# SM3320-BATT-EV.net
KiCad netlist of a schematic drawn in Altium Designer
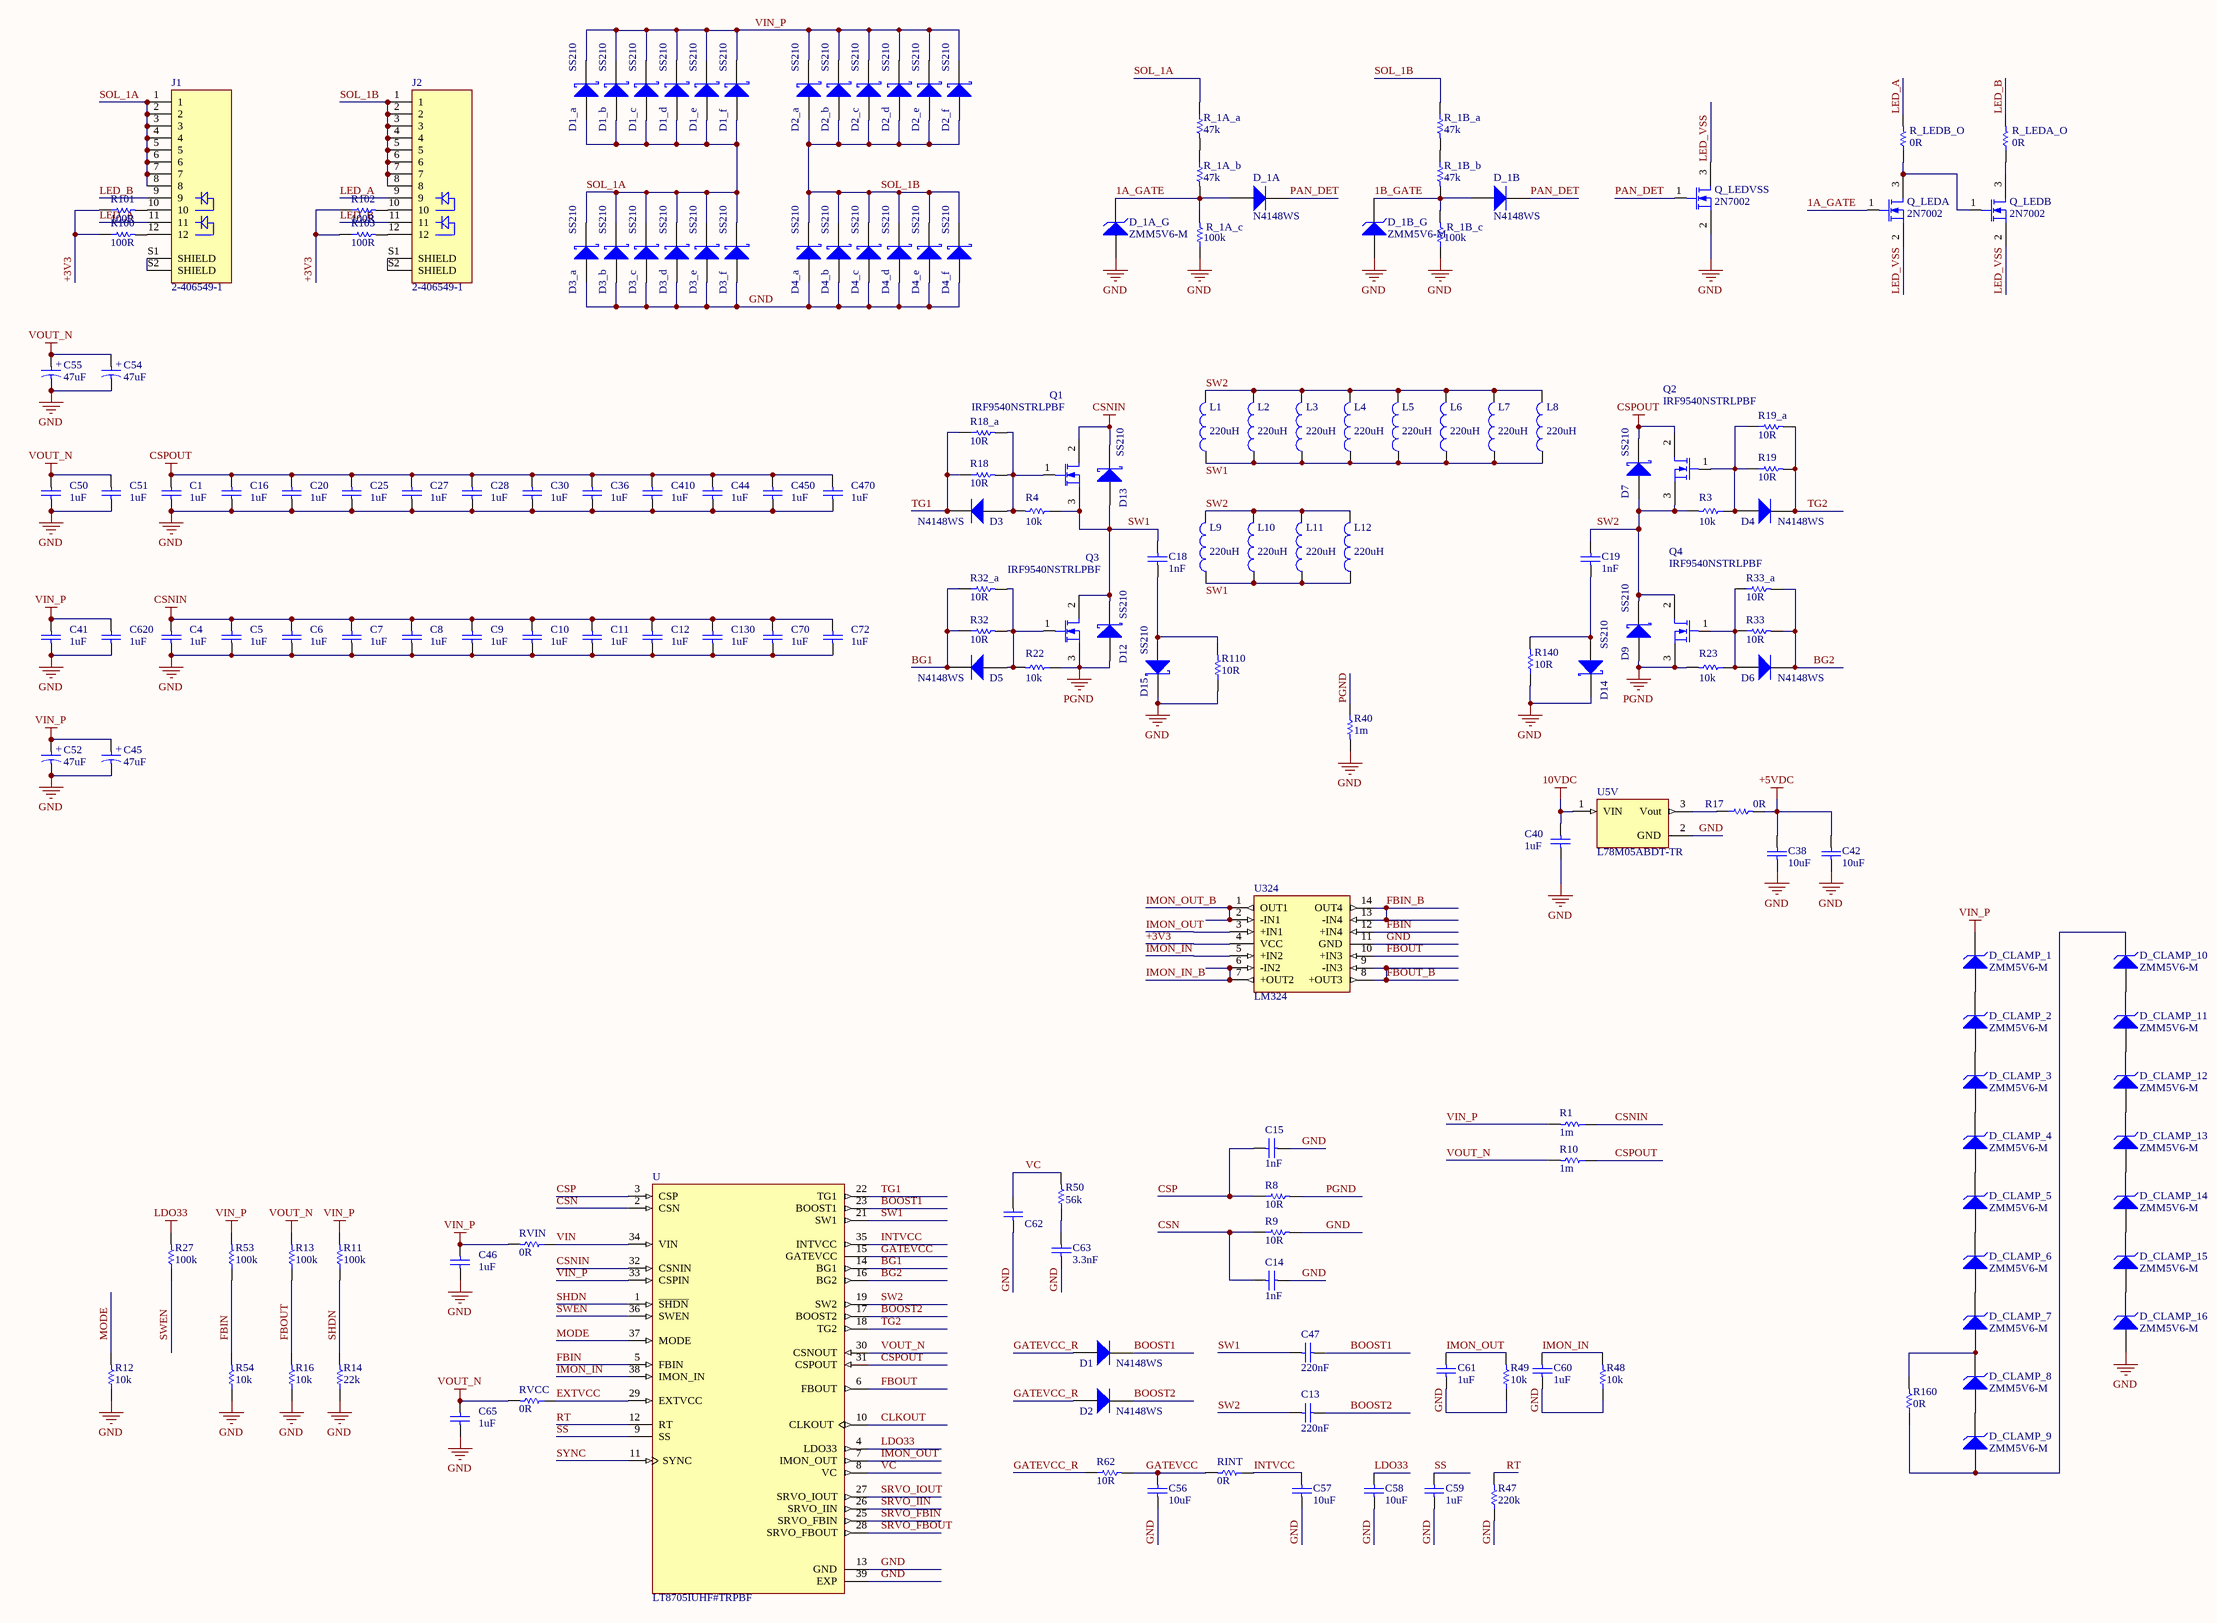
[diagram p0: SM3320-BATT-EV.SchDoc]

(export (version "E")
  (design (tool "Eeschema 10.0.6"))
  (components
    (comp (ref "C1")
      (value "1uF")
      (footprint "C_1206")
      (description "C - CAPACITOR - MLCC - 1uF - 100V - 1206 - X7R")
      (fields (field (name "LCSC PART #") "C91151") (field (name "Comment") "1206B105K101NT"))
      (libsource (lib "JLC_PCB") (part "1206B105K101NT"))
    )
    (comp (ref "C4")
      (value "1uF")
      (footprint "C_1206")
      (description "C - CAPACITOR - MLCC - 1uF - 100V - 1206 - X7R")
      (fields (field (name "LCSC PART #") "C91151") (field (name "Comment") "1206B105K101NT"))
      (libsource (lib "JLC_PCB") (part "1206B105K101NT"))
    )
    (comp (ref "C5")
      (value "1uF")
      (footprint "C_1206")
      (description "C - CAPACITOR - MLCC - 1uF - 100V - 1206 - X7R")
      (fields (field (name "LCSC PART #") "C91151") (field (name "Comment") "1206B105K101NT"))
      (libsource (lib "JLC_PCB") (part "1206B105K101NT"))
    )
    (comp (ref "C6")
      (value "1uF")
      (footprint "C_1206")
      (description "C - CAPACITOR - MLCC - 1uF - 100V - 1206 - X7R")
      (fields (field (name "LCSC PART #") "C91151") (field (name "Comment") "1206B105K101NT"))
      (libsource (lib "JLC_PCB") (part "1206B105K101NT"))
    )
    (comp (ref "C7")
      (value "1uF")
      (footprint "C_1206")
      (description "C - CAPACITOR - MLCC - 1uF - 100V - 1206 - X7R")
      (fields (field (name "LCSC PART #") "C91151") (field (name "Comment") "1206B105K101NT"))
      (libsource (lib "JLC_PCB") (part "1206B105K101NT"))
    )
    (comp (ref "C8")
      (value "1uF")
      (footprint "C_1206")
      (description "C - CAPACITOR - MLCC - 1uF - 100V - 1206 - X7R")
      (fields (field (name "LCSC PART #") "C91151") (field (name "Comment") "1206B105K101NT"))
      (libsource (lib "JLC_PCB") (part "1206B105K101NT"))
    )
    (comp (ref "C9")
      (value "1uF")
      (footprint "C_1206")
      (description "C - CAPACITOR - MLCC - 1uF - 100V - 1206 - X7R")
      (fields (field (name "LCSC PART #") "C91151") (field (name "Comment") "1206B105K101NT"))
      (libsource (lib "JLC_PCB") (part "1206B105K101NT"))
    )
    (comp (ref "C10")
      (value "1uF")
      (footprint "C_1206")
      (description "C - CAPACITOR - MLCC - 1uF - 100V - 1206 - X7R")
      (fields (field (name "LCSC PART #") "C91151") (field (name "Comment") "1206B105K101NT"))
      (libsource (lib "JLC_PCB") (part "1206B105K101NT"))
    )
    (comp (ref "C11")
      (value "1uF")
      (footprint "C_1206")
      (description "C - CAPACITOR - MLCC - 1uF - 100V - 1206 - X7R")
      (fields (field (name "LCSC PART #") "C91151") (field (name "Comment") "1206B105K101NT"))
      (libsource (lib "JLC_PCB") (part "1206B105K101NT"))
    )
    (comp (ref "C12")
      (value "1uF")
      (footprint "C_1206")
      (description "C - CAPACITOR - MLCC - 1uF - 100V - 1206 - X7R")
      (fields (field (name "LCSC PART #") "C91151") (field (name "Comment") "1206B105K101NT"))
      (libsource (lib "JLC_PCB") (part "1206B105K101NT"))
    )
    (comp (ref "C13")
      (value "220nF")
      (footprint "C_0402")
      (description "C - CAPACITOR - MLCC - 220nF - 16V - 0402")
      (fields (field (name "LCSC PART #") "C16772") (field (name "Comment") "CL05B224KO5NNNC"))
      (libsource (lib "JLC_PCB") (part "CL05B224KO5NNNC"))
    )
    (comp (ref "C14")
      (value "1nF")
      (footprint "C_0402")
      (description "C - CAPACITOR - MLCC - 1nF - 50V - 0402")
      (fields (field (name "LCSC PART #") "C1523") (field (name "Comment") "0402B102K500NT"))
      (libsource (lib "JLC_PCB") (part "0402B102K500NT"))
    )
    (comp (ref "C15")
      (value "1nF")
      (footprint "C_0402")
      (description "C - CAPACITOR - MLCC - 1nF - 50V - 0402")
      (fields (field (name "LCSC PART #") "C1523") (field (name "Comment") "0402B102K500NT"))
      (libsource (lib "JLC_PCB") (part "0402B102K500NT"))
    )
    (comp (ref "C16")
      (value "1uF")
      (footprint "C_1206")
      (description "C - CAPACITOR - MLCC - 1uF - 100V - 1206 - X7R")
      (fields (field (name "LCSC PART #") "C91151") (field (name "Comment") "1206B105K101NT"))
      (libsource (lib "JLC_PCB") (part "1206B105K101NT"))
    )
    (comp (ref "C18")
      (value "1nF")
      (footprint "C_1206")
      (description "C - CAPACITOR - MLCC - 1nF - 2000V - 1206 - X7R")
      (fields (field (name "LCSC PART #") "C9196") (field (name "Comment") "1206B102K202NT"))
      (libsource (lib "JLC_PCB") (part "1206B102K202NT"))
    )
    (comp (ref "C19")
      (value "1nF")
      (footprint "C_1206")
      (description "C - CAPACITOR - MLCC - 1nF - 2000V - 1206 - X7R")
      (fields (field (name "LCSC PART #") "C9196") (field (name "Comment") "1206B102K202NT"))
      (libsource (lib "JLC_PCB") (part "1206B102K202NT"))
    )
    (comp (ref "C20")
      (value "1uF")
      (footprint "C_1206")
      (description "C - CAPACITOR - MLCC - 1uF - 100V - 1206 - X7R")
      (fields (field (name "LCSC PART #") "C91151") (field (name "Comment") "1206B105K101NT"))
      (libsource (lib "JLC_PCB") (part "1206B105K101NT"))
    )
    (comp (ref "C25")
      (value "1uF")
      (footprint "C_1206")
      (description "C - CAPACITOR - MLCC - 1uF - 100V - 1206 - X7R")
      (fields (field (name "LCSC PART #") "C91151") (field (name "Comment") "1206B105K101NT"))
      (libsource (lib "JLC_PCB") (part "1206B105K101NT"))
    )
    (comp (ref "C27")
      (value "1uF")
      (footprint "C_1206")
      (description "C - CAPACITOR - MLCC - 1uF - 100V - 1206 - X7R")
      (fields (field (name "LCSC PART #") "C91151") (field (name "Comment") "1206B105K101NT"))
      (libsource (lib "JLC_PCB") (part "1206B105K101NT"))
    )
    (comp (ref "C28")
      (value "1uF")
      (footprint "C_1206")
      (description "C - CAPACITOR - MLCC - 1uF - 100V - 1206 - X7R")
      (fields (field (name "LCSC PART #") "C91151") (field (name "Comment") "1206B105K101NT"))
      (libsource (lib "JLC_PCB") (part "1206B105K101NT"))
    )
    (comp (ref "C30")
      (value "1uF")
      (footprint "C_1206")
      (description "C - CAPACITOR - MLCC - 1uF - 100V - 1206 - X7R")
      (fields (field (name "LCSC PART #") "C91151") (field (name "Comment") "1206B105K101NT"))
      (libsource (lib "JLC_PCB") (part "1206B105K101NT"))
    )
    (comp (ref "C36")
      (value "1uF")
      (footprint "C_1206")
      (description "C - CAPACITOR - MLCC - 1uF - 100V - 1206 - X7R")
      (fields (field (name "LCSC PART #") "C91151") (field (name "Comment") "1206B105K101NT"))
      (libsource (lib "JLC_PCB") (part "1206B105K101NT"))
    )
    (comp (ref "C38")
      (value "10uF")
      (footprint "C_0402")
      (description "C - CAPACITOR - MLCC - 10uF - 6.3V - 0402")
      (fields (field (name "LCSC PART #") "C15525") (field (name "Comment") "CL05A106MQ5NUNC"))
      (libsource (lib "JLC_PCB") (part "CL05A106MQ5NUNC"))
    )
    (comp (ref "C40")
      (value "1uF")
      (footprint "C_0402")
      (description "C - CAPACITOR - MLCC - 1uF - 25V - 0402")
      (fields (field (name "LCSC PART #") "C52923") (field (name "Comment") "CL05A105KA5NQNC"))
      (libsource (lib "JLC_PCB") (part "CL05A105KA5NQNC"))
    )
    (comp (ref "C41")
      (value "1uF")
      (footprint "C_1206")
      (description "C - CAPACITOR - MLCC - 1uF - 100V - 1206 - X7R")
      (fields (field (name "LCSC PART #") "C91151") (field (name "Comment") "1206B105K101NT"))
      (libsource (lib "JLC_PCB") (part "1206B105K101NT"))
    )
    (comp (ref "C42")
      (value "10uF")
      (footprint "C_0402")
      (description "C - CAPACITOR - MLCC - 10uF - 6.3V - 0402")
      (fields (field (name "LCSC PART #") "C15525") (field (name "Comment") "CL05A106MQ5NUNC"))
      (libsource (lib "JLC_PCB") (part "CL05A106MQ5NUNC"))
    )
    (comp (ref "C44")
      (value "1uF")
      (footprint "C_1206")
      (description "C - CAPACITOR - MLCC - 1uF - 100V - 1206 - X7R")
      (fields (field (name "LCSC PART #") "C91151") (field (name "Comment") "1206B105K101NT"))
      (libsource (lib "JLC_PCB") (part "1206B105K101NT"))
    )
    (comp (ref "C45")
      (value "47uF")
      (footprint "C_CAN_1010")
      (description "C - CAPACITOR - ELECTROLYTIC - 47uF - 100V")
      (fields (field (name "LCSC PART #") "C164068") (field (name "Comment") "VZH470M2ATR-1010"))
      (libsource (lib "JLC_PCB") (part "VZH470M2ATR-1010"))
    )
    (comp (ref "C46")
      (value "1uF")
      (footprint "C_1206")
      (description "C - CAPACITOR - MLCC - 1uF - 100V - 1206 - X7R")
      (fields (field (name "LCSC PART #") "C91151") (field (name "Comment") "1206B105K101NT"))
      (libsource (lib "JLC_PCB") (part "1206B105K101NT"))
    )
    (comp (ref "C47")
      (value "220nF")
      (footprint "C_0402")
      (description "C - CAPACITOR - MLCC - 220nF - 16V - 0402")
      (fields (field (name "LCSC PART #") "C16772") (field (name "Comment") "CL05B224KO5NNNC"))
      (libsource (lib "JLC_PCB") (part "CL05B224KO5NNNC"))
    )
    (comp (ref "C50")
      (value "1uF")
      (footprint "C_1206")
      (description "C - CAPACITOR - MLCC - 1uF - 100V - 1206 - X7R")
      (fields (field (name "LCSC PART #") "C91151") (field (name "Comment") "1206B105K101NT"))
      (libsource (lib "JLC_PCB") (part "1206B105K101NT"))
    )
    (comp (ref "C51")
      (value "1uF")
      (footprint "C_1206")
      (description "C - CAPACITOR - MLCC - 1uF - 100V - 1206 - X7R")
      (fields (field (name "LCSC PART #") "C91151") (field (name "Comment") "1206B105K101NT"))
      (libsource (lib "JLC_PCB") (part "1206B105K101NT"))
    )
    (comp (ref "C52")
      (value "47uF")
      (footprint "C_CAN_1010")
      (description "C - CAPACITOR - ELECTROLYTIC - 47uF - 100V")
      (fields (field (name "LCSC PART #") "C164068") (field (name "Comment") "VZH470M2ATR-1010"))
      (libsource (lib "JLC_PCB") (part "VZH470M2ATR-1010"))
    )
    (comp (ref "C54")
      (value "47uF")
      (footprint "C_CAN_1010")
      (description "C - CAPACITOR - ELECTROLYTIC - 47uF - 100V")
      (fields (field (name "LCSC PART #") "C164068") (field (name "Comment") "VZH470M2ATR-1010"))
      (libsource (lib "JLC_PCB") (part "VZH470M2ATR-1010"))
    )
    (comp (ref "C55")
      (value "47uF")
      (footprint "C_CAN_1010")
      (description "C - CAPACITOR - ELECTROLYTIC - 47uF - 100V")
      (fields (field (name "LCSC PART #") "C164068") (field (name "Comment") "VZH470M2ATR-1010"))
      (libsource (lib "JLC_PCB") (part "VZH470M2ATR-1010"))
    )
    (comp (ref "C56")
      (value "10uF")
      (footprint "C_0402")
      (description "C - CAPACITOR - MLCC - 10uF - 6.3V - 0402")
      (fields (field (name "LCSC PART #") "C15525") (field (name "Comment") "CL05A106MQ5NUNC"))
      (libsource (lib "JLC_PCB") (part "CL05A106MQ5NUNC"))
    )
    (comp (ref "C57")
      (value "10uF")
      (footprint "C_0402")
      (description "C - CAPACITOR - MLCC - 10uF - 6.3V - 0402")
      (fields (field (name "LCSC PART #") "C15525") (field (name "Comment") "CL05A106MQ5NUNC"))
      (libsource (lib "JLC_PCB") (part "CL05A106MQ5NUNC"))
    )
    (comp (ref "C58")
      (value "10uF")
      (footprint "C_0402")
      (description "C - CAPACITOR - MLCC - 10uF - 6.3V - 0402")
      (fields (field (name "LCSC PART #") "C15525") (field (name "Comment") "CL05A106MQ5NUNC"))
      (libsource (lib "JLC_PCB") (part "CL05A106MQ5NUNC"))
    )
    (comp (ref "C59")
      (value "1uF")
      (footprint "C_0402")
      (description "C - CAPACITOR - MLCC - 1uF - 25V - 0402")
      (fields (field (name "LCSC PART #") "C52923") (field (name "Comment") "CL05A105KA5NQNC"))
      (libsource (lib "JLC_PCB") (part "CL05A105KA5NQNC"))
    )
    (comp (ref "C60")
      (value "1uF")
      (footprint "C_0402")
      (description "C - CAPACITOR - MLCC - 1uF - 25V - 0402")
      (fields (field (name "LCSC PART #") "C52923") (field (name "Comment") "CL05A105KA5NQNC"))
      (libsource (lib "JLC_PCB") (part "CL05A105KA5NQNC"))
    )
    (comp (ref "C61")
      (value "1uF")
      (footprint "C_0402")
      (description "C - CAPACITOR - MLCC - 1uF - 25V - 0402")
      (fields (field (name "LCSC PART #") "C52923") (field (name "Comment") "CL05A105KA5NQNC"))
      (libsource (lib "JLC_PCB") (part "CL05A105KA5NQNC"))
    )
    (comp (ref "C62")
      (value "0402CG101J500NT")
      (footprint "C_0402")
      (description "C - CAPACITOR - MLCC - 100pF - 50V - 0402")
      (fields (field (name "LCSC PART #") "C1546"))
      (libsource (lib "JLC_PCB") (part "0402CG101J500NT"))
    )
    (comp (ref "C63")
      (value "3.3nF")
      (footprint "C_0402")
      (description "C - CAPACITOR - MLCC - 3.3nF - 50V - 0402")
      (fields (field (name "LCSC PART #") "C26404") (field (name "Comment") "CL05B332KB5NNNC"))
      (libsource (lib "JLC_PCB") (part "CL05B332KB5NNNC"))
    )
    (comp (ref "C65")
      (value "1uF")
      (footprint "C_1206")
      (description "C - CAPACITOR - MLCC - 1uF - 100V - 1206 - X7R")
      (fields (field (name "LCSC PART #") "C91151") (field (name "Comment") "1206B105K101NT"))
      (libsource (lib "JLC_PCB") (part "1206B105K101NT"))
    )
    (comp (ref "C70")
      (value "1uF")
      (footprint "C_1206")
      (description "C - CAPACITOR - MLCC - 1uF - 100V - 1206 - X7R")
      (fields (field (name "LCSC PART #") "C91151") (field (name "Comment") "1206B105K101NT"))
      (libsource (lib "JLC_PCB") (part "1206B105K101NT"))
    )
    (comp (ref "C72")
      (value "1uF")
      (footprint "C_1206")
      (description "C - CAPACITOR - MLCC - 1uF - 100V - 1206 - X7R")
      (fields (field (name "LCSC PART #") "C91151") (field (name "Comment") "1206B105K101NT"))
      (libsource (lib "JLC_PCB") (part "1206B105K101NT"))
    )
    (comp (ref "C130")
      (value "1uF")
      (footprint "C_1206")
      (description "C - CAPACITOR - MLCC - 1uF - 100V - 1206 - X7R")
      (fields (field (name "LCSC PART #") "C91151") (field (name "Comment") "1206B105K101NT"))
      (libsource (lib "JLC_PCB") (part "1206B105K101NT"))
    )
    (comp (ref "C410")
      (value "1uF")
      (footprint "C_1206")
      (description "C - CAPACITOR - MLCC - 1uF - 100V - 1206 - X7R")
      (fields (field (name "LCSC PART #") "C91151") (field (name "Comment") "1206B105K101NT"))
      (libsource (lib "JLC_PCB") (part "1206B105K101NT"))
    )
    (comp (ref "C450")
      (value "1uF")
      (footprint "C_1206")
      (description "C - CAPACITOR - MLCC - 1uF - 100V - 1206 - X7R")
      (fields (field (name "LCSC PART #") "C91151") (field (name "Comment") "1206B105K101NT"))
      (libsource (lib "JLC_PCB") (part "1206B105K101NT"))
    )
    (comp (ref "C470")
      (value "1uF")
      (footprint "C_1206")
      (description "C - CAPACITOR - MLCC - 1uF - 100V - 1206 - X7R")
      (fields (field (name "LCSC PART #") "C91151") (field (name "Comment") "1206B105K101NT"))
      (libsource (lib "JLC_PCB") (part "1206B105K101NT"))
    )
    (comp (ref "C620")
      (value "1uF")
      (footprint "C_1206")
      (description "C - CAPACITOR - MLCC - 1uF - 100V - 1206 - X7R")
      (fields (field (name "LCSC PART #") "C91151") (field (name "Comment") "1206B105K101NT"))
      (libsource (lib "JLC_PCB") (part "1206B105K101NT"))
    )
    (comp (ref "D1")
      (value "N4148WS")
      (footprint "SOD-323")
      (description "D - DIODE - FAST TRR - 100V - 150mA - 4ns")
      (fields (field (name "LCSC PART #") "C2128"))
      (libsource (lib "JLC_PCB") (part "N4148WS"))
    )
    (comp (ref "D1_a")
      (value "SS210")
      (footprint "DO-214AC")
      (description "D - DIODE - SCHOTTKY - 100V - 2A")
      (fields (field (name "LCSC PART #") "C14996"))
      (libsource (lib "JLC_PCB") (part "SS210"))
    )
    (comp (ref "D1_b")
      (value "SS210")
      (footprint "DO-214AC")
      (description "D - DIODE - SCHOTTKY - 100V - 2A")
      (fields (field (name "LCSC PART #") "C14996"))
      (libsource (lib "JLC_PCB") (part "SS210"))
    )
    (comp (ref "D1_c")
      (value "SS210")
      (footprint "DO-214AC")
      (description "D - DIODE - SCHOTTKY - 100V - 2A")
      (fields (field (name "LCSC PART #") "C14996"))
      (libsource (lib "JLC_PCB") (part "SS210"))
    )
    (comp (ref "D1_d")
      (value "SS210")
      (footprint "DO-214AC")
      (description "D - DIODE - SCHOTTKY - 100V - 2A")
      (fields (field (name "LCSC PART #") "C14996"))
      (libsource (lib "JLC_PCB") (part "SS210"))
    )
    (comp (ref "D1_e")
      (value "SS210")
      (footprint "DO-214AC")
      (description "D - DIODE - SCHOTTKY - 100V - 2A")
      (fields (field (name "LCSC PART #") "C14996"))
      (libsource (lib "JLC_PCB") (part "SS210"))
    )
    (comp (ref "D1_f")
      (value "SS210")
      (footprint "DO-214AC")
      (description "D - DIODE - SCHOTTKY - 100V - 2A")
      (fields (field (name "LCSC PART #") "C14996"))
      (libsource (lib "JLC_PCB") (part "SS210"))
    )
    (comp (ref "D2")
      (value "N4148WS")
      (footprint "SOD-323")
      (description "D - DIODE - FAST TRR - 100V - 150mA - 4ns")
      (fields (field (name "LCSC PART #") "C2128"))
      (libsource (lib "JLC_PCB") (part "N4148WS"))
    )
    (comp (ref "D2_a")
      (value "SS210")
      (footprint "DO-214AC")
      (description "D - DIODE - SCHOTTKY - 100V - 2A")
      (fields (field (name "LCSC PART #") "C14996"))
      (libsource (lib "JLC_PCB") (part "SS210"))
    )
    (comp (ref "D2_b")
      (value "SS210")
      (footprint "DO-214AC")
      (description "D - DIODE - SCHOTTKY - 100V - 2A")
      (fields (field (name "LCSC PART #") "C14996"))
      (libsource (lib "JLC_PCB") (part "SS210"))
    )
    (comp (ref "D2_c")
      (value "SS210")
      (footprint "DO-214AC")
      (description "D - DIODE - SCHOTTKY - 100V - 2A")
      (fields (field (name "LCSC PART #") "C14996"))
      (libsource (lib "JLC_PCB") (part "SS210"))
    )
    (comp (ref "D2_d")
      (value "SS210")
      (footprint "DO-214AC")
      (description "D - DIODE - SCHOTTKY - 100V - 2A")
      (fields (field (name "LCSC PART #") "C14996"))
      (libsource (lib "JLC_PCB") (part "SS210"))
    )
    (comp (ref "D2_e")
      (value "SS210")
      (footprint "DO-214AC")
      (description "D - DIODE - SCHOTTKY - 100V - 2A")
      (fields (field (name "LCSC PART #") "C14996"))
      (libsource (lib "JLC_PCB") (part "SS210"))
    )
    (comp (ref "D2_f")
      (value "SS210")
      (footprint "DO-214AC")
      (description "D - DIODE - SCHOTTKY - 100V - 2A")
      (fields (field (name "LCSC PART #") "C14996"))
      (libsource (lib "JLC_PCB") (part "SS210"))
    )
    (comp (ref "D3")
      (value "N4148WS")
      (footprint "SOD-323")
      (description "D - DIODE - FAST TRR - 100V - 150mA - 4ns")
      (fields (field (name "LCSC PART #") "C2128"))
      (libsource (lib "JLC_PCB") (part "N4148WS"))
    )
    (comp (ref "D3_a")
      (value "SS210")
      (footprint "DO-214AC")
      (description "D - DIODE - SCHOTTKY - 100V - 2A")
      (fields (field (name "LCSC PART #") "C14996"))
      (libsource (lib "JLC_PCB") (part "SS210"))
    )
    (comp (ref "D3_b")
      (value "SS210")
      (footprint "DO-214AC")
      (description "D - DIODE - SCHOTTKY - 100V - 2A")
      (fields (field (name "LCSC PART #") "C14996"))
      (libsource (lib "JLC_PCB") (part "SS210"))
    )
    (comp (ref "D3_c")
      (value "SS210")
      (footprint "DO-214AC")
      (description "D - DIODE - SCHOTTKY - 100V - 2A")
      (fields (field (name "LCSC PART #") "C14996"))
      (libsource (lib "JLC_PCB") (part "SS210"))
    )
    (comp (ref "D3_d")
      (value "SS210")
      (footprint "DO-214AC")
      (description "D - DIODE - SCHOTTKY - 100V - 2A")
      (fields (field (name "LCSC PART #") "C14996"))
      (libsource (lib "JLC_PCB") (part "SS210"))
    )
    (comp (ref "D3_e")
      (value "SS210")
      (footprint "DO-214AC")
      (description "D - DIODE - SCHOTTKY - 100V - 2A")
      (fields (field (name "LCSC PART #") "C14996"))
      (libsource (lib "JLC_PCB") (part "SS210"))
    )
    (comp (ref "D3_f")
      (value "SS210")
      (footprint "DO-214AC")
      (description "D - DIODE - SCHOTTKY - 100V - 2A")
      (fields (field (name "LCSC PART #") "C14996"))
      (libsource (lib "JLC_PCB") (part "SS210"))
    )
    (comp (ref "D4")
      (value "N4148WS")
      (footprint "SOD-323")
      (description "D - DIODE - FAST TRR - 100V - 150mA - 4ns")
      (fields (field (name "LCSC PART #") "C2128"))
      (libsource (lib "JLC_PCB") (part "N4148WS"))
    )
    (comp (ref "D4_a")
      (value "SS210")
      (footprint "DO-214AC")
      (description "D - DIODE - SCHOTTKY - 100V - 2A")
      (fields (field (name "LCSC PART #") "C14996"))
      (libsource (lib "JLC_PCB") (part "SS210"))
    )
    (comp (ref "D4_b")
      (value "SS210")
      (footprint "DO-214AC")
      (description "D - DIODE - SCHOTTKY - 100V - 2A")
      (fields (field (name "LCSC PART #") "C14996"))
      (libsource (lib "JLC_PCB") (part "SS210"))
    )
    (comp (ref "D4_c")
      (value "SS210")
      (footprint "DO-214AC")
      (description "D - DIODE - SCHOTTKY - 100V - 2A")
      (fields (field (name "LCSC PART #") "C14996"))
      (libsource (lib "JLC_PCB") (part "SS210"))
    )
    (comp (ref "D4_d")
      (value "SS210")
      (footprint "DO-214AC")
      (description "D - DIODE - SCHOTTKY - 100V - 2A")
      (fields (field (name "LCSC PART #") "C14996"))
      (libsource (lib "JLC_PCB") (part "SS210"))
    )
    (comp (ref "D4_e")
      (value "SS210")
      (footprint "DO-214AC")
      (description "D - DIODE - SCHOTTKY - 100V - 2A")
      (fields (field (name "LCSC PART #") "C14996"))
      (libsource (lib "JLC_PCB") (part "SS210"))
    )
    (comp (ref "D4_f")
      (value "SS210")
      (footprint "DO-214AC")
      (description "D - DIODE - SCHOTTKY - 100V - 2A")
      (fields (field (name "LCSC PART #") "C14996"))
      (libsource (lib "JLC_PCB") (part "SS210"))
    )
    (comp (ref "D5")
      (value "N4148WS")
      (footprint "SOD-323")
      (description "D - DIODE - FAST TRR - 100V - 150mA - 4ns")
      (fields (field (name "LCSC PART #") "C2128"))
      (libsource (lib "JLC_PCB") (part "N4148WS"))
    )
    (comp (ref "D6")
      (value "N4148WS")
      (footprint "SOD-323")
      (description "D - DIODE - FAST TRR - 100V - 150mA - 4ns")
      (fields (field (name "LCSC PART #") "C2128"))
      (libsource (lib "JLC_PCB") (part "N4148WS"))
    )
    (comp (ref "D7")
      (value "SS210")
      (footprint "DO-214AC")
      (description "D - DIODE - SCHOTTKY - 100V - 2A")
      (fields (field (name "LCSC PART #") "C14996"))
      (libsource (lib "JLC_PCB") (part "SS210"))
    )
    (comp (ref "D9")
      (value "SS210")
      (footprint "DO-214AC")
      (description "D - DIODE - SCHOTTKY - 100V - 2A")
      (fields (field (name "LCSC PART #") "C14996"))
      (libsource (lib "JLC_PCB") (part "SS210"))
    )
    (comp (ref "D12")
      (value "SS210")
      (footprint "DO-214AC")
      (description "D - DIODE - SCHOTTKY - 100V - 2A")
      (fields (field (name "LCSC PART #") "C14996"))
      (libsource (lib "JLC_PCB") (part "SS210"))
    )
    (comp (ref "D13")
      (value "SS210")
      (footprint "DO-214AC")
      (description "D - DIODE - SCHOTTKY - 100V - 2A")
      (fields (field (name "LCSC PART #") "C14996"))
      (libsource (lib "JLC_PCB") (part "SS210"))
    )
    (comp (ref "D14")
      (value "SS210")
      (footprint "DO-214AC")
      (description "D - DIODE - SCHOTTKY - 100V - 2A")
      (fields (field (name "LCSC PART #") "C14996"))
      (libsource (lib "JLC_PCB") (part "SS210"))
    )
    (comp (ref "D15")
      (value "SS210")
      (footprint "DO-214AC")
      (description "D - DIODE - SCHOTTKY - 100V - 2A")
      (fields (field (name "LCSC PART #") "C14996"))
      (libsource (lib "JLC_PCB") (part "SS210"))
    )
    (comp (ref "D_1A")
      (value "N4148WS")
      (footprint "SOD-323")
      (description "D - DIODE - FAST TRR - 100V - 150mA - 4ns")
      (fields (field (name "LCSC PART #") "C2128"))
      (libsource (lib "JLC_PCB") (part "N4148WS"))
    )
    (comp (ref "D_1A_G")
      (value "ZMM5V6-M")
      (footprint "DO-213AA")
      (description "D - DIODE - ZENER - 5.6V - 500mW")
      (fields (field (name "LCSC PART #") "C8062"))
      (libsource (lib "JLC_PCB") (part "ZMM5V6-M"))
    )
    (comp (ref "D_1B")
      (value "N4148WS")
      (footprint "SOD-323")
      (description "D - DIODE - FAST TRR - 100V - 150mA - 4ns")
      (fields (field (name "LCSC PART #") "C2128"))
      (libsource (lib "JLC_PCB") (part "N4148WS"))
    )
    (comp (ref "D_1B_G")
      (value "ZMM5V6-M")
      (footprint "DO-213AA")
      (description "D - DIODE - ZENER - 5.6V - 500mW")
      (fields (field (name "LCSC PART #") "C8062"))
      (libsource (lib "JLC_PCB") (part "ZMM5V6-M"))
    )
    (comp (ref "D_CLAMP_1")
      (value "ZMM5V6-M")
      (footprint "DO-213AA")
      (description "D - DIODE - ZENER - 5.6V - 500mW")
      (fields (field (name "LCSC PART #") "C8062"))
      (libsource (lib "JLC_PCB") (part "ZMM5V6-M"))
    )
    (comp (ref "D_CLAMP_2")
      (value "ZMM5V6-M")
      (footprint "DO-213AA")
      (description "D - DIODE - ZENER - 5.6V - 500mW")
      (fields (field (name "LCSC PART #") "C8062"))
      (libsource (lib "JLC_PCB") (part "ZMM5V6-M"))
    )
    (comp (ref "D_CLAMP_3")
      (value "ZMM5V6-M")
      (footprint "DO-213AA")
      (description "D - DIODE - ZENER - 5.6V - 500mW")
      (fields (field (name "LCSC PART #") "C8062"))
      (libsource (lib "JLC_PCB") (part "ZMM5V6-M"))
    )
    (comp (ref "D_CLAMP_4")
      (value "ZMM5V6-M")
      (footprint "DO-213AA")
      (description "D - DIODE - ZENER - 5.6V - 500mW")
      (fields (field (name "LCSC PART #") "C8062"))
      (libsource (lib "JLC_PCB") (part "ZMM5V6-M"))
    )
    (comp (ref "D_CLAMP_5")
      (value "ZMM5V6-M")
      (footprint "DO-213AA")
      (description "D - DIODE - ZENER - 5.6V - 500mW")
      (fields (field (name "LCSC PART #") "C8062"))
      (libsource (lib "JLC_PCB") (part "ZMM5V6-M"))
    )
    (comp (ref "D_CLAMP_6")
      (value "ZMM5V6-M")
      (footprint "DO-213AA")
      (description "D - DIODE - ZENER - 5.6V - 500mW")
      (fields (field (name "LCSC PART #") "C8062"))
      (libsource (lib "JLC_PCB") (part "ZMM5V6-M"))
    )
    (comp (ref "D_CLAMP_7")
      (value "ZMM5V6-M")
      (footprint "DO-213AA")
      (description "D - DIODE - ZENER - 5.6V - 500mW")
      (fields (field (name "LCSC PART #") "C8062"))
      (libsource (lib "JLC_PCB") (part "ZMM5V6-M"))
    )
    (comp (ref "D_CLAMP_8")
      (value "ZMM5V6-M")
      (footprint "DO-213AA")
      (description "D - DIODE - ZENER - 5.6V - 500mW")
      (fields (field (name "LCSC PART #") "C8062"))
      (libsource (lib "JLC_PCB") (part "ZMM5V6-M"))
    )
    (comp (ref "D_CLAMP_9")
      (value "ZMM5V6-M")
      (footprint "DO-213AA")
      (description "D - DIODE - ZENER - 5.6V - 500mW")
      (fields (field (name "LCSC PART #") "C8062"))
      (libsource (lib "JLC_PCB") (part "ZMM5V6-M"))
    )
    (comp (ref "D_CLAMP_10")
      (value "ZMM5V6-M")
      (footprint "DO-213AA")
      (description "D - DIODE - ZENER - 5.6V - 500mW")
      (fields (field (name "LCSC PART #") "C8062"))
      (libsource (lib "JLC_PCB") (part "ZMM5V6-M"))
    )
    (comp (ref "D_CLAMP_11")
      (value "ZMM5V6-M")
      (footprint "DO-213AA")
      (description "D - DIODE - ZENER - 5.6V - 500mW")
      (fields (field (name "LCSC PART #") "C8062"))
      (libsource (lib "JLC_PCB") (part "ZMM5V6-M"))
    )
    (comp (ref "D_CLAMP_12")
      (value "ZMM5V6-M")
      (footprint "DO-213AA")
      (description "D - DIODE - ZENER - 5.6V - 500mW")
      (fields (field (name "LCSC PART #") "C8062"))
      (libsource (lib "JLC_PCB") (part "ZMM5V6-M"))
    )
    (comp (ref "D_CLAMP_13")
      (value "ZMM5V6-M")
      (footprint "DO-213AA")
      (description "D - DIODE - ZENER - 5.6V - 500mW")
      (fields (field (name "LCSC PART #") "C8062"))
      (libsource (lib "JLC_PCB") (part "ZMM5V6-M"))
    )
    (comp (ref "D_CLAMP_14")
      (value "ZMM5V6-M")
      (footprint "DO-213AA")
      (description "D - DIODE - ZENER - 5.6V - 500mW")
      (fields (field (name "LCSC PART #") "C8062"))
      (libsource (lib "JLC_PCB") (part "ZMM5V6-M"))
    )
    (comp (ref "D_CLAMP_15")
      (value "ZMM5V6-M")
      (footprint "DO-213AA")
      (description "D - DIODE - ZENER - 5.6V - 500mW")
      (fields (field (name "LCSC PART #") "C8062"))
      (libsource (lib "JLC_PCB") (part "ZMM5V6-M"))
    )
    (comp (ref "D_CLAMP_16")
      (value "ZMM5V6-M")
      (footprint "DO-213AA")
      (description "D - DIODE - ZENER - 5.6V - 500mW")
      (fields (field (name "LCSC PART #") "C8062"))
      (libsource (lib "JLC_PCB") (part "ZMM5V6-M"))
    )
    (comp (ref "J1")
      (value "2-406549-1")
      (footprint "TE_2-406549-1")
      (description "J - JACK - ETHERNET - Right - THT")
      (fields (field (name "LCSC PART #") "C125068"))
      (libsource (lib "JLC_PCB") (part "2-406549-1"))
    )
    (comp (ref "J2")
      (value "2-406549-1")
      (footprint "TE_2-406549-1")
      (description "J - JACK - ETHERNET - Right - THT")
      (fields (field (name "LCSC PART #") "C125068"))
      (libsource (lib "JLC_PCB") (part "2-406549-1"))
    )
    (comp (ref "L1")
      (value "220uH")
      (footprint "SRR1260")
      (description "L - INDUCTOR - 220uH - 1.6A - 12.5mm")
      (fields (field (name "LCSC PART #") "C169380") (field (name "Comment") "SWRB1207S-221MT"))
      (libsource (lib "JLC_PCB") (part "SWRB1207S-221MT"))
    )
    (comp (ref "L2")
      (value "220uH")
      (footprint "SRR1260")
      (description "L - INDUCTOR - 220uH - 1.6A - 12.5mm")
      (fields (field (name "LCSC PART #") "C169380") (field (name "Comment") "SWRB1207S-221MT"))
      (libsource (lib "JLC_PCB") (part "SWRB1207S-221MT"))
    )
    (comp (ref "L3")
      (value "220uH")
      (footprint "SRR1260")
      (description "L - INDUCTOR - 220uH - 1.6A - 12.5mm")
      (fields (field (name "LCSC PART #") "C169380") (field (name "Comment") "SWRB1207S-221MT"))
      (libsource (lib "JLC_PCB") (part "SWRB1207S-221MT"))
    )
    (comp (ref "L4")
      (value "220uH")
      (footprint "SRR1260")
      (description "L - INDUCTOR - 220uH - 1.6A - 12.5mm")
      (fields (field (name "LCSC PART #") "C169380") (field (name "Comment") "SWRB1207S-221MT"))
      (libsource (lib "JLC_PCB") (part "SWRB1207S-221MT"))
    )
    (comp (ref "L5")
      (value "220uH")
      (footprint "SRR1260")
      (description "L - INDUCTOR - 220uH - 1.6A - 12.5mm")
      (fields (field (name "LCSC PART #") "C169380") (field (name "Comment") "SWRB1207S-221MT"))
      (libsource (lib "JLC_PCB") (part "SWRB1207S-221MT"))
    )
    (comp (ref "L6")
      (value "220uH")
      (footprint "SRR1260")
      (description "L - INDUCTOR - 220uH - 1.6A - 12.5mm")
      (fields (field (name "LCSC PART #") "C169380") (field (name "Comment") "SWRB1207S-221MT"))
      (libsource (lib "JLC_PCB") (part "SWRB1207S-221MT"))
    )
    (comp (ref "L7")
      (value "220uH")
      (footprint "SRR1260")
      (description "L - INDUCTOR - 220uH - 1.6A - 12.5mm")
      (fields (field (name "LCSC PART #") "C169380") (field (name "Comment") "SWRB1207S-221MT"))
      (libsource (lib "JLC_PCB") (part "SWRB1207S-221MT"))
    )
    (comp (ref "L8")
      (value "220uH")
      (footprint "SRR1260")
      (description "L - INDUCTOR - 220uH - 1.6A - 12.5mm")
      (fields (field (name "LCSC PART #") "C169380") (field (name "Comment") "SWRB1207S-221MT"))
      (libsource (lib "JLC_PCB") (part "SWRB1207S-221MT"))
    )
    (comp (ref "L9")
      (value "220uH")
      (footprint "SRR1260")
      (description "L - INDUCTOR - 220uH - 1.6A - 12.5mm")
      (fields (field (name "LCSC PART #") "C169380") (field (name "Comment") "SWRB1207S-221MT"))
      (libsource (lib "JLC_PCB") (part "SWRB1207S-221MT"))
    )
    (comp (ref "L10")
      (value "220uH")
      (footprint "SRR1260")
      (description "L - INDUCTOR - 220uH - 1.6A - 12.5mm")
      (fields (field (name "LCSC PART #") "C169380") (field (name "Comment") "SWRB1207S-221MT"))
      (libsource (lib "JLC_PCB") (part "SWRB1207S-221MT"))
    )
    (comp (ref "L11")
      (value "220uH")
      (footprint "SRR1260")
      (description "L - INDUCTOR - 220uH - 1.6A - 12.5mm")
      (fields (field (name "LCSC PART #") "C169380") (field (name "Comment") "SWRB1207S-221MT"))
      (libsource (lib "JLC_PCB") (part "SWRB1207S-221MT"))
    )
    (comp (ref "L12")
      (value "220uH")
      (footprint "SRR1260")
      (description "L - INDUCTOR - 220uH - 1.6A - 12.5mm")
      (fields (field (name "LCSC PART #") "C169380") (field (name "Comment") "SWRB1207S-221MT"))
      (libsource (lib "JLC_PCB") (part "SWRB1207S-221MT"))
    )
    (comp (ref "Q1")
      (value "IRF9540NSTRLPBF")
      (footprint "TO-263-3")
      (description "Q - TRANSISTOR - MOSFET (N) - 250V - 33A - 0.094R")
      (fields (field (name "LCSC PART #") "C33903"))
      (libsource (lib "JLC_PCB") (part "IRF9540NSTRLPBF"))
    )
    (comp (ref "Q2")
      (value "IRF9540NSTRLPBF")
      (footprint "TO-263-3")
      (description "Q - TRANSISTOR - MOSFET (N) - 250V - 33A - 0.094R")
      (fields (field (name "LCSC PART #") "C33903"))
      (libsource (lib "JLC_PCB") (part "IRF9540NSTRLPBF"))
    )
    (comp (ref "Q3")
      (value "IRF9540NSTRLPBF")
      (footprint "TO-263-3")
      (description "Q - TRANSISTOR - MOSFET (N) - 250V - 33A - 0.094R")
      (fields (field (name "LCSC PART #") "C33903"))
      (libsource (lib "JLC_PCB") (part "IRF9540NSTRLPBF"))
    )
    (comp (ref "Q4")
      (value "IRF9540NSTRLPBF")
      (footprint "TO-263-3")
      (description "Q - TRANSISTOR - MOSFET (N) - 250V - 33A - 0.094R")
      (fields (field (name "LCSC PART #") "C33903"))
      (libsource (lib "JLC_PCB") (part "IRF9540NSTRLPBF"))
    )
    (comp (ref "Q_LEDA")
      (value "2N7002")
      (footprint "TO-236AB")
      (description "Q - TRANSISTOR - MOSFET (N) - 60V - 200mW")
      (fields (field (name "LCSC PART #") "C8545"))
      (libsource (lib "JLC_PCB") (part "2N7002"))
    )
    (comp (ref "Q_LEDB")
      (value "2N7002")
      (footprint "TO-236AB")
      (description "Q - TRANSISTOR - MOSFET (N) - 60V - 200mW")
      (fields (field (name "LCSC PART #") "C8545"))
      (libsource (lib "JLC_PCB") (part "2N7002"))
    )
    (comp (ref "Q_LEDVSS")
      (value "2N7002")
      (footprint "TO-236AB")
      (description "Q - TRANSISTOR - MOSFET (N) - 60V - 200mW")
      (fields (field (name "LCSC PART #") "C8545"))
      (libsource (lib "JLC_PCB") (part "2N7002"))
    )
    (comp (ref "R1")
      (value "1m")
      (footprint "R_2512")
      (description "R - RESISTOR - SMD - 0.001R - 1% - 2512 - 2W - 50ppm/k")
      (fields (field (name "LCSC PART #") "C349153") (field (name "POWER") "2W"))
      (libsource (lib "JLC_PCB") (part "EWSL2512F1L00S9"))
    )
    (comp (ref "R3")
      (value "10k")
      (footprint "R_0402")
      (description "R - RESISTOR - SMD - 10k - 1% - 0402")
      (fields (field (name "LCSC PART #") "C25744") (field (name "Comment") "0402WGF1002TCE"))
      (libsource (lib "JLC_PCB") (part "0402WGF1002TCE"))
    )
    (comp (ref "R4")
      (value "10k")
      (footprint "R_0402")
      (description "R - RESISTOR - SMD - 10k - 1% - 0402")
      (fields (field (name "LCSC PART #") "C25744") (field (name "Comment") "0402WGF1002TCE"))
      (libsource (lib "JLC_PCB") (part "0402WGF1002TCE"))
    )
    (comp (ref "R8")
      (value "10R")
      (footprint "R_0402")
      (description "R - RESISTOR - SMD - 10R - 1% - 0402")
      (fields (field (name "LCSC PART #") "C25077") (field (name "Comment") "0402WGF100JTCE"))
      (libsource (lib "JLC_PCB") (part "0402WGF100JTCE"))
    )
    (comp (ref "R9")
      (value "10R")
      (footprint "R_0402")
      (description "R - RESISTOR - SMD - 10R - 1% - 0402")
      (fields (field (name "LCSC PART #") "C25077") (field (name "Comment") "0402WGF100JTCE"))
      (libsource (lib "JLC_PCB") (part "0402WGF100JTCE"))
    )
    (comp (ref "R10")
      (value "1m")
      (footprint "R_2512")
      (description "R - RESISTOR - SMD - 0.001R - 1% - 2512 - 2W - 50ppm/k")
      (fields (field (name "LCSC PART #") "C349153") (field (name "POWER") "2W"))
      (libsource (lib "JLC_PCB") (part "EWSL2512F1L00S9"))
    )
    (comp (ref "R11")
      (value "100k")
      (footprint "R_0603")
      (description "R - RESISTOR - SMD - 100k - 1% -  0603")
      (fields (field (name "LCSC PART #") "C22936") (field (name "Comment") "0603WAF100KT5E"))
      (libsource (lib "JLC_PCB") (part "0603WAF100KT5E"))
    )
    (comp (ref "R12")
      (value "10k")
      (footprint "R_0402")
      (description "R - RESISTOR - SMD - 10k - 1% - 0402")
      (fields (field (name "LCSC PART #") "C25744") (field (name "Comment") "0402WGF1002TCE"))
      (libsource (lib "JLC_PCB") (part "0402WGF1002TCE"))
    )
    (comp (ref "R13")
      (value "100k")
      (footprint "R_0603")
      (description "R - RESISTOR - SMD - 100k - 1% -  0603")
      (fields (field (name "LCSC PART #") "C22936") (field (name "Comment") "0603WAF100KT5E"))
      (libsource (lib "JLC_PCB") (part "0603WAF100KT5E"))
    )
    (comp (ref "R14")
      (value "22k")
      (footprint "R_0402")
      (description "R - RESISTOR - SMD - 22k - 1% - 0402")
      (fields (field (name "LCSC PART #") "C25768") (field (name "Comment") "0402WGF2202TCE"))
      (libsource (lib "JLC_PCB") (part "0402WGF2202TCE"))
    )
    (comp (ref "R16")
      (value "10k")
      (footprint "R_0603")
      (description "R - RESISTOR - SMD - 10k - 1% - 0603")
      (fields (field (name "LCSC PART #") "C25804") (field (name "Comment") "0603WAF1002T5E"))
      (libsource (lib "JLC_PCB") (part "0603WAF1002T5E"))
    )
    (comp (ref "R17")
      (value "0R")
      (footprint "R_0402")
      (description "R - RESISTOR - SMD - 0R - 1% - 0402")
      (fields (field (name "LCSC PART #") "C17168") (field (name "Comment") "0402WGF0000TCE"))
      (libsource (lib "JLC_PCB") (part "0402WGF0000TCE"))
    )
    (comp (ref "R18")
      (value "10R")
      (footprint "R_0402")
      (description "R - RESISTOR - SMD - 10R - 1% - 0402")
      (fields (field (name "LCSC PART #") "C25077") (field (name "Comment") "0402WGF100JTCE"))
      (libsource (lib "JLC_PCB") (part "0402WGF100JTCE"))
    )
    (comp (ref "R18_a")
      (value "10R")
      (footprint "R_0402")
      (description "R - RESISTOR - SMD - 10R - 1% - 0402")
      (fields (field (name "LCSC PART #") "C25077") (field (name "Comment") "0402WGF100JTCE"))
      (libsource (lib "JLC_PCB") (part "0402WGF100JTCE"))
    )
    (comp (ref "R19")
      (value "10R")
      (footprint "R_0402")
      (description "R - RESISTOR - SMD - 10R - 1% - 0402")
      (fields (field (name "LCSC PART #") "C25077") (field (name "Comment") "0402WGF100JTCE"))
      (libsource (lib "JLC_PCB") (part "0402WGF100JTCE"))
    )
    (comp (ref "R19_a")
      (value "10R")
      (footprint "R_0402")
      (description "R - RESISTOR - SMD - 10R - 1% - 0402")
      (fields (field (name "LCSC PART #") "C25077") (field (name "Comment") "0402WGF100JTCE"))
      (libsource (lib "JLC_PCB") (part "0402WGF100JTCE"))
    )
    (comp (ref "R22")
      (value "10k")
      (footprint "R_0402")
      (description "R - RESISTOR - SMD - 10k - 1% - 0402")
      (fields (field (name "LCSC PART #") "C25744") (field (name "Comment") "0402WGF1002TCE"))
      (libsource (lib "JLC_PCB") (part "0402WGF1002TCE"))
    )
    (comp (ref "R23")
      (value "10k")
      (footprint "R_0402")
      (description "R - RESISTOR - SMD - 10k - 1% - 0402")
      (fields (field (name "LCSC PART #") "C25744") (field (name "Comment") "0402WGF1002TCE"))
      (libsource (lib "JLC_PCB") (part "0402WGF1002TCE"))
    )
    (comp (ref "R27")
      (value "100k")
      (footprint "R_0402")
      (description "R - RESISTOR - SMD - 100k - 1% -  0402")
      (fields (field (name "LCSC PART #") "C25741") (field (name "Comment") "0402WGF1003TCE"))
      (libsource (lib "JLC_PCB") (part "0402WGF1003TCE"))
    )
    (comp (ref "R32")
      (value "10R")
      (footprint "R_0402")
      (description "R - RESISTOR - SMD - 10R - 1% - 0402")
      (fields (field (name "LCSC PART #") "C25077") (field (name "Comment") "0402WGF100JTCE"))
      (libsource (lib "JLC_PCB") (part "0402WGF100JTCE"))
    )
    (comp (ref "R32_a")
      (value "10R")
      (footprint "R_0402")
      (description "R - RESISTOR - SMD - 10R - 1% - 0402")
      (fields (field (name "LCSC PART #") "C25077") (field (name "Comment") "0402WGF100JTCE"))
      (libsource (lib "JLC_PCB") (part "0402WGF100JTCE"))
    )
    (comp (ref "R33")
      (value "10R")
      (footprint "R_0402")
      (description "R - RESISTOR - SMD - 10R - 1% - 0402")
      (fields (field (name "LCSC PART #") "C25077") (field (name "Comment") "0402WGF100JTCE"))
      (libsource (lib "JLC_PCB") (part "0402WGF100JTCE"))
    )
    (comp (ref "R33_a")
      (value "10R")
      (footprint "R_0402")
      (description "R - RESISTOR - SMD - 10R - 1% - 0402")
      (fields (field (name "LCSC PART #") "C25077") (field (name "Comment") "0402WGF100JTCE"))
      (libsource (lib "JLC_PCB") (part "0402WGF100JTCE"))
    )
    (comp (ref "R40")
      (value "1m")
      (footprint "R_2512")
      (description "R - RESISTOR - SMD - 0.001R - 1% - 2512 - 2W - 50ppm/k")
      (fields (field (name "LCSC PART #") "C349153") (field (name "POWER") "2W"))
      (libsource (lib "JLC_PCB") (part "EWSL2512F1L00S9"))
    )
    (comp (ref "R47")
      (value "220k")
      (footprint "R_0402")
      (description "R - RESISTOR - SMD - 220k - 1% - 0402")
      (fields (field (name "LCSC PART #") "C25767") (field (name "Comment") "0402WGF2203TCE"))
      (libsource (lib "JLC_PCB") (part "0402WGF2203TCE"))
    )
    (comp (ref "R48")
      (value "10k")
      (footprint "R_0603")
      (description "R - RESISTOR - SMD - 10k - 1% - 0603")
      (fields (field (name "LCSC PART #") "C25804") (field (name "Comment") "0603WAF1002T5E"))
      (libsource (lib "JLC_PCB") (part "0603WAF1002T5E"))
    )
    (comp (ref "R49")
      (value "10k")
      (footprint "R_0603")
      (description "R - RESISTOR - SMD - 10k - 1% - 0603")
      (fields (field (name "LCSC PART #") "C25804") (field (name "Comment") "0603WAF1002T5E"))
      (libsource (lib "JLC_PCB") (part "0603WAF1002T5E"))
    )
    (comp (ref "R50")
      (value "56k")
      (footprint "R_0402")
      (description "R - RESISTOR - SMD - 56k - 1% - 0402")
      (fields (field (name "LCSC PART #") "C25796") (field (name "Comment") "0402WGF5602TCE"))
      (libsource (lib "JLC_PCB") (part "0402WGF5602TCE"))
    )
    (comp (ref "R53")
      (value "100k")
      (footprint "R_0603")
      (description "R - RESISTOR - SMD - 100k - 1% -  0603")
      (fields (field (name "LCSC PART #") "C22936") (field (name "Comment") "0603WAF100KT5E"))
      (libsource (lib "JLC_PCB") (part "0603WAF100KT5E"))
    )
    (comp (ref "R54")
      (value "10k")
      (footprint "R_0603")
      (description "R - RESISTOR - SMD - 10k - 1% - 0603")
      (fields (field (name "LCSC PART #") "C25804") (field (name "Comment") "0603WAF1002T5E"))
      (libsource (lib "JLC_PCB") (part "0603WAF1002T5E"))
    )
    (comp (ref "R62")
      (value "10R")
      (footprint "R_0402")
      (description "R - RESISTOR - SMD - 10R - 1% - 0402")
      (fields (field (name "LCSC PART #") "C25077") (field (name "Comment") "0402WGF100JTCE"))
      (libsource (lib "JLC_PCB") (part "0402WGF100JTCE"))
    )
    (comp (ref "R100")
      (value "100R")
      (footprint "R_0402")
      (description "R - RESISTOR - SMD - 100R - 1% - 0402")
      (fields (field (name "LCSC PART #") "C25076") (field (name "Comment") "0402WGF1000TCE"))
      (libsource (lib "JLC_PCB") (part "0402WGF1000TCE"))
    )
    (comp (ref "R101")
      (value "100R")
      (footprint "R_0402")
      (description "R - RESISTOR - SMD - 100R - 1% - 0402")
      (fields (field (name "LCSC PART #") "C25076") (field (name "Comment") "0402WGF1000TCE"))
      (libsource (lib "JLC_PCB") (part "0402WGF1000TCE"))
    )
    (comp (ref "R102")
      (value "100R")
      (footprint "R_0402")
      (description "R - RESISTOR - SMD - 100R - 1% - 0402")
      (fields (field (name "LCSC PART #") "C25076") (field (name "Comment") "0402WGF1000TCE"))
      (libsource (lib "JLC_PCB") (part "0402WGF1000TCE"))
    )
    (comp (ref "R103")
      (value "100R")
      (footprint "R_0402")
      (description "R - RESISTOR - SMD - 100R - 1% - 0402")
      (fields (field (name "LCSC PART #") "C25076") (field (name "Comment") "0402WGF1000TCE"))
      (libsource (lib "JLC_PCB") (part "0402WGF1000TCE"))
    )
    (comp (ref "R110")
      (value "10R")
      (footprint "R_1206")
      (description "R - RESISTOR - SMD - 10R - 1% - 1206")
      (fields (field (name "LCSC PART #") "C17903") (field (name "Comment") "1206W4F100JT5E"))
      (libsource (lib "JLC_PCB") (part "1206W4F100JT5E"))
    )
    (comp (ref "R140")
      (value "10R")
      (footprint "R_1206")
      (description "R - RESISTOR - SMD - 10R - 1% - 1206")
      (fields (field (name "LCSC PART #") "C17903") (field (name "Comment") "1206W4F100JT5E"))
      (libsource (lib "JLC_PCB") (part "1206W4F100JT5E"))
    )
    (comp (ref "R160")
      (value "0R")
      (footprint "R_0402")
      (description "R - RESISTOR - SMD - 0R - 1% - 0402")
      (fields (field (name "LCSC PART #") "C17168") (field (name "Comment") "0402WGF0000TCE"))
      (libsource (lib "JLC_PCB") (part "0402WGF0000TCE"))
    )
    (comp (ref "RINT")
      (value "0R")
      (footprint "R_0402")
      (description "R - RESISTOR - SMD - 0R - 1% - 0402")
      (fields (field (name "LCSC PART #") "C17168") (field (name "Comment") "0402WGF0000TCE"))
      (libsource (lib "JLC_PCB") (part "0402WGF0000TCE"))
    )
    (comp (ref "RVCC")
      (value "0R")
      (footprint "R_0402")
      (description "R - RESISTOR - SMD - 0R - 1% - 0402")
      (fields (field (name "LCSC PART #") "C17168") (field (name "Comment") "0402WGF0000TCE"))
      (libsource (lib "JLC_PCB") (part "0402WGF0000TCE"))
    )
    (comp (ref "RVIN")
      (value "0R")
      (footprint "R_0402")
      (description "R - RESISTOR - SMD - 0R - 1% - 0402")
      (fields (field (name "LCSC PART #") "C17168") (field (name "Comment") "0402WGF0000TCE"))
      (libsource (lib "JLC_PCB") (part "0402WGF0000TCE"))
    )
    (comp (ref "R_1A_a")
      (value "47k")
      (footprint "R_0402")
      (description "R - RESISTOR - SMD - 47k - 1% - 0402")
      (fields (field (name "LCSC PART #") "C25792") (field (name "Comment") "0402WGF4702TCE"))
      (libsource (lib "JLC_PCB") (part "0402WGF4702TCE"))
    )
    (comp (ref "R_1A_b")
      (value "47k")
      (footprint "R_0402")
      (description "R - RESISTOR - SMD - 47k - 1% - 0402")
      (fields (field (name "LCSC PART #") "C25792") (field (name "Comment") "0402WGF4702TCE"))
      (libsource (lib "JLC_PCB") (part "0402WGF4702TCE"))
    )
    (comp (ref "R_1A_c")
      (value "100k")
      (footprint "R_0402")
      (description "R - RESISTOR - SMD - 100k - 1% -  0402")
      (fields (field (name "LCSC PART #") "C25741") (field (name "Comment") "0402WGF1003TCE"))
      (libsource (lib "JLC_PCB") (part "0402WGF1003TCE"))
    )
    (comp (ref "R_1B_a")
      (value "47k")
      (footprint "R_0402")
      (description "R - RESISTOR - SMD - 47k - 1% - 0402")
      (fields (field (name "LCSC PART #") "C25792") (field (name "Comment") "0402WGF4702TCE"))
      (libsource (lib "JLC_PCB") (part "0402WGF4702TCE"))
    )
    (comp (ref "R_1B_b")
      (value "47k")
      (footprint "R_0402")
      (description "R - RESISTOR - SMD - 47k - 1% - 0402")
      (fields (field (name "LCSC PART #") "C25792") (field (name "Comment") "0402WGF4702TCE"))
      (libsource (lib "JLC_PCB") (part "0402WGF4702TCE"))
    )
    (comp (ref "R_1B_c")
      (value "100k")
      (footprint "R_0402")
      (description "R - RESISTOR - SMD - 100k - 1% -  0402")
      (fields (field (name "LCSC PART #") "C25741") (field (name "Comment") "0402WGF1003TCE"))
      (libsource (lib "JLC_PCB") (part "0402WGF1003TCE"))
    )
    (comp (ref "R_LEDA_O")
      (value "0R")
      (footprint "R_0402")
      (description "R - RESISTOR - SMD - 0R - 1% - 0402")
      (fields (field (name "LCSC PART #") "C17168") (field (name "Comment") "0402WGF0000TCE"))
      (libsource (lib "JLC_PCB") (part "0402WGF0000TCE"))
    )
    (comp (ref "R_LEDB_O")
      (value "0R")
      (footprint "R_0402")
      (description "R - RESISTOR - SMD - 0R - 1% - 0402")
      (fields (field (name "LCSC PART #") "C17168") (field (name "Comment") "0402WGF0000TCE"))
      (libsource (lib "JLC_PCB") (part "0402WGF0000TCE"))
    )
    (comp (ref "U")
      (value "LT8705IUHF#TRPBF")
      (footprint "QFN-39-P0.5MM")
      (description "DC/DC Cntrlr Single-OUT Step Down/Step Up 400kHz Automotive 38-Pin QFN EP T/R")
      (fields (field (name "MP") "LT8705AIUHF#TRPBF") (field (name "LCSC PART #") "C674170"))
      (libsource (lib "JLC_PCB") (part "LT8705IUHF#TRPBF"))
    )
    (comp (ref "U5V")
      (value "L78M05ABDT-TR")
      (footprint "TO-252AA")
      (description "U - IC - 5V Power Regulator")
      (fields (field (name "LCSC PART #") "C58069"))
      (libsource (lib "JLC_PCB") (part "L78M05ABDT-TR"))
    )
    (comp (ref "U324")
      (value "LM324")
      (footprint "SILICON:SOIC-14-P1.27-W3.5")
      (description "U - IC - OP AMP (QUAD)")
      (fields (field (name "LCSC PART #") "C71035"))
      (libsource (lib "*") (part "LM324DT"))
    )
  )
  (nets
    (net (code "1") (name "+5VDC") (class "Default")
      (node (ref "C38") (pin "2") (pinfunction "2_2") (pintype "passive"))
      (node (ref "C42") (pin "2") (pinfunction "2_2") (pintype "passive"))
      (node (ref "R17") (pin "2") (pinfunction "2_2") (pintype "passive"))
    )
    (net (code "2") (name "/+3V3") (class "Default")
      (node (ref "R100") (pin "1") (pinfunction "1_1") (pintype "passive"))
      (node (ref "R101") (pin "1") (pinfunction "1_1") (pintype "passive"))
      (node (ref "R102") (pin "1") (pinfunction "1_1") (pintype "passive"))
      (node (ref "R103") (pin "1") (pinfunction "1_1") (pintype "passive"))
      (node (ref "U324") (pin "4") (pinfunction "VCC_4") (pintype "power_in"))
    )
    (net (code "3") (name "/1A_GATE") (class "Default")
      (node (ref "D_1A") (pin "2") (pinfunction "A_2") (pintype "passive"))
      (node (ref "D_1A_G") (pin "1") (pinfunction "K_1") (pintype "passive"))
      (node (ref "Q_LEDA") (pin "1") (pinfunction "G_1") (pintype "passive"))
      (node (ref "R_1A_b") (pin "2") (pinfunction "2_2") (pintype "passive"))
      (node (ref "R_1A_c") (pin "2") (pinfunction "2_2") (pintype "passive"))
    )
    (net (code "4") (name "/1B_GATE") (class "Default")
      (node (ref "D_1B") (pin "2") (pinfunction "A_2") (pintype "passive"))
      (node (ref "D_1B_G") (pin "1") (pinfunction "K_1") (pintype "passive"))
      (node (ref "R_1B_b") (pin "2") (pinfunction "2_2") (pintype "passive"))
      (node (ref "R_1B_c") (pin "2") (pinfunction "2_2") (pintype "passive"))
    )
    (net (code "5") (name "/BG1") (class "Default")
      (node (ref "D5") (pin "1") (pinfunction "K_1") (pintype "passive"))
      (node (ref "R32") (pin "1") (pinfunction "1_1") (pintype "passive"))
      (node (ref "R32_a") (pin "1") (pinfunction "1_1") (pintype "passive"))
      (node (ref "U") (pin "14") (pinfunction "BG1_14") (pintype "output"))
    )
    (net (code "6") (name "/BG2") (class "Default")
      (node (ref "D6") (pin "1") (pinfunction "K_1") (pintype "passive"))
      (node (ref "R33") (pin "2") (pinfunction "2_2") (pintype "passive"))
      (node (ref "R33_a") (pin "2") (pinfunction "2_2") (pintype "passive"))
      (node (ref "U") (pin "16") (pinfunction "BG2_16") (pintype "output"))
    )
    (net (code "7") (name "/BOOST1") (class "Default")
      (node (ref "C47") (pin "2") (pinfunction "2_2") (pintype "passive"))
      (node (ref "D1") (pin "1") (pinfunction "K_1") (pintype "passive"))
      (node (ref "U") (pin "23") (pinfunction "BOOST1_23") (pintype "output"))
    )
    (net (code "8") (name "/BOOST2") (class "Default")
      (node (ref "C13") (pin "2") (pinfunction "2_2") (pintype "passive"))
      (node (ref "D2") (pin "1") (pinfunction "K_1") (pintype "passive"))
      (node (ref "U") (pin "17") (pinfunction "BOOST2_17") (pintype "output"))
    )
    (net (code "9") (name "/CLKOUT") (class "Default")
      (node (ref "U") (pin "10") (pinfunction "CLKOUT_10") (pintype "output"))
    )
    (net (code "10") (name "/CSN") (class "Default")
      (node (ref "C14") (pin "1") (pinfunction "1_1") (pintype "passive"))
      (node (ref "R9") (pin "1") (pinfunction "1_1") (pintype "passive"))
      (node (ref "U") (pin "2") (pinfunction "CSN_2") (pintype "input"))
    )
    (net (code "11") (name "/CSP") (class "Default")
      (node (ref "C15") (pin "1") (pinfunction "1_1") (pintype "passive"))
      (node (ref "R8") (pin "1") (pinfunction "1_1") (pintype "passive"))
      (node (ref "U") (pin "3") (pinfunction "CSP_3") (pintype "input"))
    )
    (net (code "12") (name "/EXTVCC") (class "Default")
      (node (ref "RVCC") (pin "1") (pinfunction "1_1") (pintype "passive"))
      (node (ref "U") (pin "29") (pinfunction "EXTVCC_29") (pintype "input"))
    )
    (net (code "13") (name "/FBIN") (class "Default")
      (node (ref "R53") (pin "1") (pinfunction "1_1") (pintype "passive"))
      (node (ref "R54") (pin "2") (pinfunction "2_2") (pintype "passive"))
      (node (ref "U") (pin "5") (pinfunction "FBIN_5") (pintype "input"))
      (node (ref "U324") (pin "12") (pinfunction "+IN4_12") (pintype "input"))
    )
    (net (code "14") (name "/FBIN_B") (class "Default")
      (node (ref "U324") (pin "13") (pinfunction "-IN4_13") (pintype "input"))
      (node (ref "U324") (pin "14") (pinfunction "OUT4_14") (pintype "output"))
    )
    (net (code "15") (name "/FBOUT") (class "Default")
      (node (ref "R13") (pin "1") (pinfunction "1_1") (pintype "passive"))
      (node (ref "R16") (pin "2") (pinfunction "2_2") (pintype "passive"))
      (node (ref "U") (pin "6") (pinfunction "FBOUT_6") (pintype "output"))
      (node (ref "U324") (pin "10") (pinfunction "+IN3_10") (pintype "input"))
    )
    (net (code "16") (name "/FBOUT_B") (class "Default")
      (node (ref "U324") (pin "8") (pinfunction "+OUT3_8") (pintype "output"))
      (node (ref "U324") (pin "9") (pinfunction "-IN3_9") (pintype "input"))
    )
    (net (code "17") (name "/GATEVCC") (class "Default")
      (node (ref "C56") (pin "2") (pinfunction "2_2") (pintype "passive"))
      (node (ref "R62") (pin "2") (pinfunction "2_2") (pintype "passive"))
      (node (ref "RINT") (pin "2") (pinfunction "2_2") (pintype "passive"))
      (node (ref "U") (pin "15") (pinfunction "GATEVCC_15") (pintype "power_in"))
    )
    (net (code "18") (name "/GATEVCC_R") (class "Default")
      (node (ref "D1") (pin "2") (pinfunction "A_2") (pintype "passive"))
      (node (ref "D2") (pin "2") (pinfunction "A_2") (pintype "passive"))
      (node (ref "R62") (pin "1") (pinfunction "1_1") (pintype "passive"))
    )
    (net (code "19") (name "/IMON_IN") (class "Default")
      (node (ref "C60") (pin "2") (pinfunction "2_2") (pintype "passive"))
      (node (ref "R48") (pin "2") (pinfunction "2_2") (pintype "passive"))
      (node (ref "U") (pin "38") (pinfunction "IMON_IN_38") (pintype "input"))
      (node (ref "U324") (pin "5") (pinfunction "+IN2_5") (pintype "input"))
    )
    (net (code "20") (name "/IMON_IN_B") (class "Default")
      (node (ref "U324") (pin "6") (pinfunction "-IN2_6") (pintype "input"))
      (node (ref "U324") (pin "7") (pinfunction "+OUT2_7") (pintype "output"))
    )
    (net (code "21") (name "/IMON_OUT") (class "Default")
      (node (ref "C61") (pin "2") (pinfunction "2_2") (pintype "passive"))
      (node (ref "R49") (pin "2") (pinfunction "2_2") (pintype "passive"))
      (node (ref "U") (pin "7") (pinfunction "IMON_OUT_7") (pintype "output"))
      (node (ref "U324") (pin "3") (pinfunction "+IN1_3") (pintype "input"))
    )
    (net (code "22") (name "/IMON_OUT_B") (class "Default")
      (node (ref "U324") (pin "1") (pinfunction "OUT1_1") (pintype "output"))
      (node (ref "U324") (pin "2") (pinfunction "-IN1_2") (pintype "input"))
    )
    (net (code "23") (name "/INTVCC") (class "Default")
      (node (ref "C57") (pin "2") (pinfunction "2_2") (pintype "passive"))
      (node (ref "RINT") (pin "1") (pinfunction "1_1") (pintype "passive"))
      (node (ref "U") (pin "35") (pinfunction "INTVCC_35") (pintype "output"))
    )
    (net (code "24") (name "/LED_A") (class "Default")
      (node (ref "J1") (pin "11") (pinfunction "11_11") (pintype "passive"))
      (node (ref "J2") (pin "9") (pinfunction "9_9") (pintype "passive"))
      (node (ref "R_LEDB_O") (pin "2") (pinfunction "2_2") (pintype "passive"))
    )
    (net (code "25") (name "/LED_B") (class "Default")
      (node (ref "J1") (pin "9") (pinfunction "9_9") (pintype "passive"))
      (node (ref "J2") (pin "11") (pinfunction "11_11") (pintype "passive"))
      (node (ref "R_LEDA_O") (pin "2") (pinfunction "2_2") (pintype "passive"))
    )
    (net (code "26") (name "/LED_VSS") (class "Default")
      (node (ref "Q_LEDA") (pin "2") (pinfunction "S_2") (pintype "passive"))
      (node (ref "Q_LEDB") (pin "2") (pinfunction "S_2") (pintype "passive"))
      (node (ref "Q_LEDVSS") (pin "3") (pinfunction "D_3") (pintype "passive"))
    )
    (net (code "27") (name "/MODE") (class "Default")
      (node (ref "R12") (pin "2") (pinfunction "2_2") (pintype "passive"))
      (node (ref "U") (pin "37") (pinfunction "MODE_37") (pintype "input"))
    )
    (net (code "28") (name "/PAN_DET") (class "Default")
      (node (ref "D_1A") (pin "1") (pinfunction "K_1") (pintype "passive"))
      (node (ref "D_1B") (pin "1") (pinfunction "K_1") (pintype "passive"))
      (node (ref "Q_LEDVSS") (pin "1") (pinfunction "G_1") (pintype "passive"))
    )
    (net (code "29") (name "/RT") (class "Default")
      (node (ref "R47") (pin "2") (pinfunction "2_2") (pintype "passive"))
      (node (ref "U") (pin "12") (pinfunction "RT_12") (pintype "passive"))
    )
    (net (code "30") (name "/SHDN") (class "Default")
      (node (ref "R11") (pin "1") (pinfunction "1_1") (pintype "passive"))
      (node (ref "R14") (pin "2") (pinfunction "2_2") (pintype "passive"))
      (node (ref "U") (pin "1") (pinfunction "~{SHDN}_1") (pintype "input"))
    )
    (net (code "31") (name "/SOL_1A") (class "Default")
      (node (ref "D1_a") (pin "2") (pinfunction "A_2") (pintype "passive"))
      (node (ref "D1_b") (pin "2") (pinfunction "A_2") (pintype "passive"))
      (node (ref "D1_c") (pin "2") (pinfunction "A_2") (pintype "passive"))
      (node (ref "D1_d") (pin "2") (pinfunction "A_2") (pintype "passive"))
      (node (ref "D1_e") (pin "2") (pinfunction "A_2") (pintype "passive"))
      (node (ref "D1_f") (pin "2") (pinfunction "A_2") (pintype "passive"))
      (node (ref "D3_a") (pin "1") (pinfunction "K_1") (pintype "passive"))
      (node (ref "D3_b") (pin "1") (pinfunction "K_1") (pintype "passive"))
      (node (ref "D3_c") (pin "1") (pinfunction "K_1") (pintype "passive"))
      (node (ref "D3_d") (pin "1") (pinfunction "K_1") (pintype "passive"))
      (node (ref "D3_e") (pin "1") (pinfunction "K_1") (pintype "passive"))
      (node (ref "D3_f") (pin "1") (pinfunction "K_1") (pintype "passive"))
      (node (ref "J1") (pin "1") (pinfunction "1_1") (pintype "passive"))
      (node (ref "J1") (pin "2") (pinfunction "2_2") (pintype "passive"))
      (node (ref "J1") (pin "3") (pinfunction "3_3") (pintype "passive"))
      (node (ref "J1") (pin "4") (pinfunction "4_4") (pintype "passive"))
      (node (ref "J1") (pin "5") (pinfunction "5_5") (pintype "passive"))
      (node (ref "J1") (pin "6") (pinfunction "6_6") (pintype "passive"))
      (node (ref "J1") (pin "7") (pinfunction "7_7") (pintype "passive"))
      (node (ref "J1") (pin "8") (pinfunction "8_8") (pintype "passive"))
      (node (ref "R_1A_a") (pin "1") (pinfunction "1_1") (pintype "passive"))
    )
    (net (code "32") (name "/SOL_1B") (class "Default")
      (node (ref "D2_a") (pin "2") (pinfunction "A_2") (pintype "passive"))
      (node (ref "D2_b") (pin "2") (pinfunction "A_2") (pintype "passive"))
      (node (ref "D2_c") (pin "2") (pinfunction "A_2") (pintype "passive"))
      (node (ref "D2_d") (pin "2") (pinfunction "A_2") (pintype "passive"))
      (node (ref "D2_e") (pin "2") (pinfunction "A_2") (pintype "passive"))
      (node (ref "D2_f") (pin "2") (pinfunction "A_2") (pintype "passive"))
      (node (ref "D4_a") (pin "1") (pinfunction "K_1") (pintype "passive"))
      (node (ref "D4_b") (pin "1") (pinfunction "K_1") (pintype "passive"))
      (node (ref "D4_c") (pin "1") (pinfunction "K_1") (pintype "passive"))
      (node (ref "D4_d") (pin "1") (pinfunction "K_1") (pintype "passive"))
      (node (ref "D4_e") (pin "1") (pinfunction "K_1") (pintype "passive"))
      (node (ref "D4_f") (pin "1") (pinfunction "K_1") (pintype "passive"))
      (node (ref "J2") (pin "1") (pinfunction "1_1") (pintype "passive"))
      (node (ref "J2") (pin "2") (pinfunction "2_2") (pintype "passive"))
      (node (ref "J2") (pin "3") (pinfunction "3_3") (pintype "passive"))
      (node (ref "J2") (pin "4") (pinfunction "4_4") (pintype "passive"))
      (node (ref "J2") (pin "5") (pinfunction "5_5") (pintype "passive"))
      (node (ref "J2") (pin "6") (pinfunction "6_6") (pintype "passive"))
      (node (ref "J2") (pin "7") (pinfunction "7_7") (pintype "passive"))
      (node (ref "J2") (pin "8") (pinfunction "8_8") (pintype "passive"))
      (node (ref "R_1B_a") (pin "1") (pinfunction "1_1") (pintype "passive"))
    )
    (net (code "33") (name "/SRVO_FBIN") (class "Default")
      (node (ref "U") (pin "25") (pinfunction "SRVO_FBIN_25") (pintype "output"))
    )
    (net (code "34") (name "/SRVO_FBOUT") (class "Default")
      (node (ref "U") (pin "28") (pinfunction "SRVO_FBOUT_28") (pintype "output"))
    )
    (net (code "35") (name "/SRVO_IIN") (class "Default")
      (node (ref "U") (pin "26") (pinfunction "SRVO_IIN_26") (pintype "output"))
    )
    (net (code "36") (name "/SRVO_IOUT") (class "Default")
      (node (ref "U") (pin "27") (pinfunction "SRVO_IOUT_27") (pintype "output"))
    )
    (net (code "37") (name "/SS") (class "Default")
      (node (ref "C59") (pin "2") (pinfunction "2_2") (pintype "passive"))
      (node (ref "U") (pin "9") (pinfunction "SS_9") (pintype "passive"))
    )
    (net (code "38") (name "/SW1") (class "Default")
      (node (ref "C18") (pin "2") (pinfunction "2_2") (pintype "passive"))
      (node (ref "C47") (pin "1") (pinfunction "1_1") (pintype "passive"))
      (node (ref "D12") (pin "1") (pinfunction "K_1") (pintype "passive"))
      (node (ref "D13") (pin "2") (pinfunction "A_2") (pintype "passive"))
      (node (ref "L1") (pin "1") (pinfunction "1_1") (pintype "passive"))
      (node (ref "L10") (pin "1") (pinfunction "1_1") (pintype "passive"))
      (node (ref "L11") (pin "1") (pinfunction "1_1") (pintype "passive"))
      (node (ref "L12") (pin "1") (pinfunction "1_1") (pintype "passive"))
      (node (ref "L2") (pin "1") (pinfunction "1_1") (pintype "passive"))
      (node (ref "L3") (pin "1") (pinfunction "1_1") (pintype "passive"))
      (node (ref "L4") (pin "1") (pinfunction "1_1") (pintype "passive"))
      (node (ref "L5") (pin "1") (pinfunction "1_1") (pintype "passive"))
      (node (ref "L6") (pin "1") (pinfunction "1_1") (pintype "passive"))
      (node (ref "L7") (pin "1") (pinfunction "1_1") (pintype "passive"))
      (node (ref "L8") (pin "1") (pinfunction "1_1") (pintype "passive"))
      (node (ref "L9") (pin "1") (pinfunction "1_1") (pintype "passive"))
      (node (ref "Q1") (pin "3") (pinfunction "S_3") (pintype "passive"))
      (node (ref "Q3") (pin "2") (pinfunction "D_2") (pintype "passive"))
      (node (ref "R4") (pin "1") (pinfunction "1_1") (pintype "passive"))
      (node (ref "U") (pin "21") (pinfunction "SW1_21") (pintype "output"))
    )
    (net (code "39") (name "/SW2") (class "Default")
      (node (ref "C13") (pin "1") (pinfunction "1_1") (pintype "passive"))
      (node (ref "C19") (pin "2") (pinfunction "2_2") (pintype "passive"))
      (node (ref "D7") (pin "2") (pinfunction "A_2") (pintype "passive"))
      (node (ref "D9") (pin "1") (pinfunction "K_1") (pintype "passive"))
      (node (ref "L1") (pin "2") (pinfunction "2_2") (pintype "passive"))
      (node (ref "L10") (pin "2") (pinfunction "2_2") (pintype "passive"))
      (node (ref "L11") (pin "2") (pinfunction "2_2") (pintype "passive"))
      (node (ref "L12") (pin "2") (pinfunction "2_2") (pintype "passive"))
      (node (ref "L2") (pin "2") (pinfunction "2_2") (pintype "passive"))
      (node (ref "L3") (pin "2") (pinfunction "2_2") (pintype "passive"))
      (node (ref "L4") (pin "2") (pinfunction "2_2") (pintype "passive"))
      (node (ref "L5") (pin "2") (pinfunction "2_2") (pintype "passive"))
      (node (ref "L6") (pin "2") (pinfunction "2_2") (pintype "passive"))
      (node (ref "L7") (pin "2") (pinfunction "2_2") (pintype "passive"))
      (node (ref "L8") (pin "2") (pinfunction "2_2") (pintype "passive"))
      (node (ref "L9") (pin "2") (pinfunction "2_2") (pintype "passive"))
      (node (ref "Q2") (pin "3") (pinfunction "S_3") (pintype "passive"))
      (node (ref "Q4") (pin "2") (pinfunction "D_2") (pintype "passive"))
      (node (ref "R3") (pin "2") (pinfunction "2_2") (pintype "passive"))
      (node (ref "U") (pin "19") (pinfunction "SW2_19") (pintype "output"))
    )
    (net (code "40") (name "/SWEN") (class "Default")
      (node (ref "R27") (pin "1") (pinfunction "1_1") (pintype "passive"))
      (node (ref "U") (pin "36") (pinfunction "SWEN_36") (pintype "input"))
    )
    (net (code "41") (name "/SYNC") (class "Default")
      (node (ref "U") (pin "11") (pinfunction "SYNC_11") (pintype "input"))
    )
    (net (code "42") (name "/TG1") (class "Default")
      (node (ref "D3") (pin "1") (pinfunction "K_1") (pintype "passive"))
      (node (ref "R18") (pin "1") (pinfunction "1_1") (pintype "passive"))
      (node (ref "R18_a") (pin "1") (pinfunction "1_1") (pintype "passive"))
      (node (ref "U") (pin "22") (pinfunction "TG1_22") (pintype "output"))
    )
    (net (code "43") (name "/TG2") (class "Default")
      (node (ref "D4") (pin "1") (pinfunction "K_1") (pintype "passive"))
      (node (ref "R19") (pin "2") (pinfunction "2_2") (pintype "passive"))
      (node (ref "R19_a") (pin "2") (pinfunction "2_2") (pintype "passive"))
      (node (ref "U") (pin "18") (pinfunction "TG2_18") (pintype "output"))
    )
    (net (code "44") (name "/VC") (class "Default")
      (node (ref "C62") (pin "2") (pinfunction "2_2") (pintype "passive"))
      (node (ref "R50") (pin "2") (pinfunction "2_2") (pintype "passive"))
      (node (ref "U") (pin "8") (pinfunction "VC_8") (pintype "output"))
    )
    (net (code "45") (name "/VIN") (class "Default")
      (node (ref "RVIN") (pin "1") (pinfunction "1_1") (pintype "passive"))
      (node (ref "U") (pin "34") (pinfunction "VIN_34") (pintype "input"))
    )
    (net (code "46") (name "10VDC") (class "Default")
      (node (ref "C40") (pin "2") (pinfunction "2_2") (pintype "passive"))
      (node (ref "U5V") (pin "1") (pinfunction "VIN_1") (pintype "input"))
    )
    (net (code "47") (name "CSNIN") (class "Default")
      (node (ref "C10") (pin "2") (pinfunction "2_2") (pintype "passive"))
      (node (ref "C11") (pin "2") (pinfunction "2_2") (pintype "passive"))
      (node (ref "C12") (pin "2") (pinfunction "2_2") (pintype "passive"))
      (node (ref "C130") (pin "2") (pinfunction "2_2") (pintype "passive"))
      (node (ref "C4") (pin "2") (pinfunction "2_2") (pintype "passive"))
      (node (ref "C5") (pin "2") (pinfunction "2_2") (pintype "passive"))
      (node (ref "C6") (pin "2") (pinfunction "2_2") (pintype "passive"))
      (node (ref "C7") (pin "2") (pinfunction "2_2") (pintype "passive"))
      (node (ref "C70") (pin "2") (pinfunction "2_2") (pintype "passive"))
      (node (ref "C72") (pin "2") (pinfunction "2_2") (pintype "passive"))
      (node (ref "C8") (pin "2") (pinfunction "2_2") (pintype "passive"))
      (node (ref "C9") (pin "2") (pinfunction "2_2") (pintype "passive"))
      (node (ref "D13") (pin "1") (pinfunction "K_1") (pintype "passive"))
      (node (ref "Q1") (pin "2") (pinfunction "D_2") (pintype "passive"))
      (node (ref "R1") (pin "1") (pinfunction "1_1") (pintype "passive"))
      (node (ref "U") (pin "32") (pinfunction "CSNIN_32") (pintype "input"))
    )
    (net (code "48") (name "CSPOUT") (class "Default")
      (node (ref "C1") (pin "2") (pinfunction "2_2") (pintype "passive"))
      (node (ref "C16") (pin "2") (pinfunction "2_2") (pintype "passive"))
      (node (ref "C20") (pin "2") (pinfunction "2_2") (pintype "passive"))
      (node (ref "C25") (pin "2") (pinfunction "2_2") (pintype "passive"))
      (node (ref "C27") (pin "2") (pinfunction "2_2") (pintype "passive"))
      (node (ref "C28") (pin "2") (pinfunction "2_2") (pintype "passive"))
      (node (ref "C30") (pin "2") (pinfunction "2_2") (pintype "passive"))
      (node (ref "C36") (pin "2") (pinfunction "2_2") (pintype "passive"))
      (node (ref "C410") (pin "2") (pinfunction "2_2") (pintype "passive"))
      (node (ref "C44") (pin "2") (pinfunction "2_2") (pintype "passive"))
      (node (ref "C450") (pin "2") (pinfunction "2_2") (pintype "passive"))
      (node (ref "C470") (pin "2") (pinfunction "2_2") (pintype "passive"))
      (node (ref "D7") (pin "1") (pinfunction "K_1") (pintype "passive"))
      (node (ref "Q2") (pin "2") (pinfunction "D_2") (pintype "passive"))
      (node (ref "R10") (pin "1") (pinfunction "1_1") (pintype "passive"))
      (node (ref "U") (pin "31") (pinfunction "CSPOUT_31") (pintype "input"))
    )
    (net (code "49") (name "GND") (class "Default")
      (node (ref "C1") (pin "1") (pinfunction "1_1") (pintype "passive"))
      (node (ref "C10") (pin "1") (pinfunction "1_1") (pintype "passive"))
      (node (ref "C11") (pin "1") (pinfunction "1_1") (pintype "passive"))
      (node (ref "C12") (pin "1") (pinfunction "1_1") (pintype "passive"))
      (node (ref "C130") (pin "1") (pinfunction "1_1") (pintype "passive"))
      (node (ref "C14") (pin "2") (pinfunction "2_2") (pintype "passive"))
      (node (ref "C15") (pin "2") (pinfunction "2_2") (pintype "passive"))
      (node (ref "C16") (pin "1") (pinfunction "1_1") (pintype "passive"))
      (node (ref "C20") (pin "1") (pinfunction "1_1") (pintype "passive"))
      (node (ref "C25") (pin "1") (pinfunction "1_1") (pintype "passive"))
      (node (ref "C27") (pin "1") (pinfunction "1_1") (pintype "passive"))
      (node (ref "C28") (pin "1") (pinfunction "1_1") (pintype "passive"))
      (node (ref "C30") (pin "1") (pinfunction "1_1") (pintype "passive"))
      (node (ref "C36") (pin "1") (pinfunction "1_1") (pintype "passive"))
      (node (ref "C38") (pin "1") (pinfunction "1_1") (pintype "passive"))
      (node (ref "C4") (pin "1") (pinfunction "1_1") (pintype "passive"))
      (node (ref "C40") (pin "1") (pinfunction "1_1") (pintype "passive"))
      (node (ref "C41") (pin "1") (pinfunction "1_1") (pintype "passive"))
      (node (ref "C410") (pin "1") (pinfunction "1_1") (pintype "passive"))
      (node (ref "C42") (pin "1") (pinfunction "1_1") (pintype "passive"))
      (node (ref "C44") (pin "1") (pinfunction "1_1") (pintype "passive"))
      (node (ref "C45") (pin "1") (pinfunction "1_1") (pintype "passive"))
      (node (ref "C450") (pin "1") (pinfunction "1_1") (pintype "passive"))
      (node (ref "C46") (pin "1") (pinfunction "1_1") (pintype "passive"))
      (node (ref "C470") (pin "1") (pinfunction "1_1") (pintype "passive"))
      (node (ref "C5") (pin "1") (pinfunction "1_1") (pintype "passive"))
      (node (ref "C50") (pin "1") (pinfunction "1_1") (pintype "passive"))
      (node (ref "C51") (pin "1") (pinfunction "1_1") (pintype "passive"))
      (node (ref "C52") (pin "1") (pinfunction "1_1") (pintype "passive"))
      (node (ref "C54") (pin "1") (pinfunction "1_1") (pintype "passive"))
      (node (ref "C55") (pin "1") (pinfunction "1_1") (pintype "passive"))
      (node (ref "C56") (pin "1") (pinfunction "1_1") (pintype "passive"))
      (node (ref "C57") (pin "1") (pinfunction "1_1") (pintype "passive"))
      (node (ref "C58") (pin "1") (pinfunction "1_1") (pintype "passive"))
      (node (ref "C59") (pin "1") (pinfunction "1_1") (pintype "passive"))
      (node (ref "C6") (pin "1") (pinfunction "1_1") (pintype "passive"))
      (node (ref "C60") (pin "1") (pinfunction "1_1") (pintype "passive"))
      (node (ref "C61") (pin "1") (pinfunction "1_1") (pintype "passive"))
      (node (ref "C62") (pin "1") (pinfunction "1_1") (pintype "passive"))
      (node (ref "C620") (pin "1") (pinfunction "1_1") (pintype "passive"))
      (node (ref "C63") (pin "1") (pinfunction "1_1") (pintype "passive"))
      (node (ref "C65") (pin "1") (pinfunction "1_1") (pintype "passive"))
      (node (ref "C7") (pin "1") (pinfunction "1_1") (pintype "passive"))
      (node (ref "C70") (pin "1") (pinfunction "1_1") (pintype "passive"))
      (node (ref "C72") (pin "1") (pinfunction "1_1") (pintype "passive"))
      (node (ref "C8") (pin "1") (pinfunction "1_1") (pintype "passive"))
      (node (ref "C9") (pin "1") (pinfunction "1_1") (pintype "passive"))
      (node (ref "D14") (pin "1") (pinfunction "K_1") (pintype "passive"))
      (node (ref "D15") (pin "1") (pinfunction "K_1") (pintype "passive"))
      (node (ref "D3_a") (pin "2") (pinfunction "A_2") (pintype "passive"))
      (node (ref "D3_b") (pin "2") (pinfunction "A_2") (pintype "passive"))
      (node (ref "D3_c") (pin "2") (pinfunction "A_2") (pintype "passive"))
      (node (ref "D3_d") (pin "2") (pinfunction "A_2") (pintype "passive"))
      (node (ref "D3_e") (pin "2") (pinfunction "A_2") (pintype "passive"))
      (node (ref "D3_f") (pin "2") (pinfunction "A_2") (pintype "passive"))
      (node (ref "D4_a") (pin "2") (pinfunction "A_2") (pintype "passive"))
      (node (ref "D4_b") (pin "2") (pinfunction "A_2") (pintype "passive"))
      (node (ref "D4_c") (pin "2") (pinfunction "A_2") (pintype "passive"))
      (node (ref "D4_d") (pin "2") (pinfunction "A_2") (pintype "passive"))
      (node (ref "D4_e") (pin "2") (pinfunction "A_2") (pintype "passive"))
      (node (ref "D4_f") (pin "2") (pinfunction "A_2") (pintype "passive"))
      (node (ref "D_1A_G") (pin "2") (pinfunction "A_2") (pintype "passive"))
      (node (ref "D_1B_G") (pin "2") (pinfunction "A_2") (pintype "passive"))
      (node (ref "D_CLAMP_16") (pin "2") (pinfunction "A_2") (pintype "passive"))
      (node (ref "Q_LEDVSS") (pin "2") (pinfunction "S_2") (pintype "passive"))
      (node (ref "R110") (pin "1") (pinfunction "1_1") (pintype "passive"))
      (node (ref "R12") (pin "1") (pinfunction "1_1") (pintype "passive"))
      (node (ref "R14") (pin "1") (pinfunction "1_1") (pintype "passive"))
      (node (ref "R140") (pin "1") (pinfunction "1_1") (pintype "passive"))
      (node (ref "R16") (pin "1") (pinfunction "1_1") (pintype "passive"))
      (node (ref "R40") (pin "2") (pinfunction "2_2") (pintype "passive"))
      (node (ref "R47") (pin "1") (pinfunction "1_1") (pintype "passive"))
      (node (ref "R48") (pin "1") (pinfunction "1_1") (pintype "passive"))
      (node (ref "R49") (pin "1") (pinfunction "1_1") (pintype "passive"))
      (node (ref "R54") (pin "1") (pinfunction "1_1") (pintype "passive"))
      (node (ref "R9") (pin "2") (pinfunction "2_2") (pintype "passive"))
      (node (ref "R_1A_c") (pin "1") (pinfunction "1_1") (pintype "passive"))
      (node (ref "R_1B_c") (pin "1") (pinfunction "1_1") (pintype "passive"))
      (node (ref "U") (pin "13") (pinfunction "GND_13") (pintype "power_in"))
      (node (ref "U") (pin "39") (pinfunction "EXP_39") (pintype "power_in"))
      (node (ref "U324") (pin "11") (pinfunction "GND_11") (pintype "power_in"))
      (node (ref "U5V") (pin "2") (pinfunction "GND_2") (pintype "power_in"))
    )
    (net (code "50") (name "LDO33") (class "Default")
      (node (ref "C58") (pin "2") (pinfunction "2_2") (pintype "passive"))
      (node (ref "R27") (pin "2") (pinfunction "2_2") (pintype "passive"))
      (node (ref "U") (pin "4") (pinfunction "LDO33_4") (pintype "output"))
    )
    (net (code "51") (name "Net-(C63-Pad2)") (class "Default")
      (node (ref "C63") (pin "2") (pinfunction "2_2") (pintype "passive"))
      (node (ref "R50") (pin "1") (pinfunction "1_1") (pintype "passive"))
    )
    (net (code "52") (name "Net-(D3-A)") (class "Default")
      (node (ref "D3") (pin "2") (pinfunction "A_2") (pintype "passive"))
      (node (ref "Q1") (pin "1") (pinfunction "G_1") (pintype "passive"))
      (node (ref "R18") (pin "2") (pinfunction "2_2") (pintype "passive"))
      (node (ref "R18_a") (pin "2") (pinfunction "2_2") (pintype "passive"))
      (node (ref "R4") (pin "2") (pinfunction "2_2") (pintype "passive"))
    )
    (net (code "53") (name "Net-(D4-A)") (class "Default")
      (node (ref "D4") (pin "2") (pinfunction "A_2") (pintype "passive"))
      (node (ref "Q2") (pin "1") (pinfunction "G_1") (pintype "passive"))
      (node (ref "R19") (pin "1") (pinfunction "1_1") (pintype "passive"))
      (node (ref "R19_a") (pin "1") (pinfunction "1_1") (pintype "passive"))
      (node (ref "R3") (pin "1") (pinfunction "1_1") (pintype "passive"))
    )
    (net (code "54") (name "Net-(D5-A)") (class "Default")
      (node (ref "D5") (pin "2") (pinfunction "A_2") (pintype "passive"))
      (node (ref "Q3") (pin "1") (pinfunction "G_1") (pintype "passive"))
      (node (ref "R22") (pin "2") (pinfunction "2_2") (pintype "passive"))
      (node (ref "R32") (pin "2") (pinfunction "2_2") (pintype "passive"))
      (node (ref "R32_a") (pin "2") (pinfunction "2_2") (pintype "passive"))
    )
    (net (code "55") (name "Net-(D6-A)") (class "Default")
      (node (ref "D6") (pin "2") (pinfunction "A_2") (pintype "passive"))
      (node (ref "Q4") (pin "1") (pinfunction "G_1") (pintype "passive"))
      (node (ref "R23") (pin "1") (pinfunction "1_1") (pintype "passive"))
      (node (ref "R33") (pin "1") (pinfunction "1_1") (pintype "passive"))
      (node (ref "R33_a") (pin "1") (pinfunction "1_1") (pintype "passive"))
    )
    (net (code "56") (name "Net-(D14-A)") (class "Default")
      (node (ref "C19") (pin "1") (pinfunction "1_1") (pintype "passive"))
      (node (ref "D14") (pin "2") (pinfunction "A_2") (pintype "passive"))
      (node (ref "R140") (pin "2") (pinfunction "2_2") (pintype "passive"))
    )
    (net (code "57") (name "Net-(D15-A)") (class "Default")
      (node (ref "C18") (pin "1") (pinfunction "1_1") (pintype "passive"))
      (node (ref "D15") (pin "2") (pinfunction "A_2") (pintype "passive"))
      (node (ref "R110") (pin "2") (pinfunction "2_2") (pintype "passive"))
    )
    (net (code "58") (name "Net-(D_CLAMP_1-A)") (class "Default")
      (node (ref "D_CLAMP_1") (pin "2") (pinfunction "A_2") (pintype "passive"))
      (node (ref "D_CLAMP_2") (pin "1") (pinfunction "K_1") (pintype "passive"))
    )
    (net (code "59") (name "Net-(D_CLAMP_2-A)") (class "Default")
      (node (ref "D_CLAMP_2") (pin "2") (pinfunction "A_2") (pintype "passive"))
      (node (ref "D_CLAMP_3") (pin "1") (pinfunction "K_1") (pintype "passive"))
    )
    (net (code "60") (name "Net-(D_CLAMP_3-A)") (class "Default")
      (node (ref "D_CLAMP_3") (pin "2") (pinfunction "A_2") (pintype "passive"))
      (node (ref "D_CLAMP_4") (pin "1") (pinfunction "K_1") (pintype "passive"))
    )
    (net (code "61") (name "Net-(D_CLAMP_4-A)") (class "Default")
      (node (ref "D_CLAMP_4") (pin "2") (pinfunction "A_2") (pintype "passive"))
      (node (ref "D_CLAMP_5") (pin "1") (pinfunction "K_1") (pintype "passive"))
    )
    (net (code "62") (name "Net-(D_CLAMP_5-A)") (class "Default")
      (node (ref "D_CLAMP_5") (pin "2") (pinfunction "A_2") (pintype "passive"))
      (node (ref "D_CLAMP_6") (pin "1") (pinfunction "K_1") (pintype "passive"))
    )
    (net (code "63") (name "Net-(D_CLAMP_6-A)") (class "Default")
      (node (ref "D_CLAMP_6") (pin "2") (pinfunction "A_2") (pintype "passive"))
      (node (ref "D_CLAMP_7") (pin "1") (pinfunction "K_1") (pintype "passive"))
    )
    (net (code "64") (name "Net-(D_CLAMP_7-A)") (class "Default")
      (node (ref "D_CLAMP_7") (pin "2") (pinfunction "A_2") (pintype "passive"))
      (node (ref "D_CLAMP_8") (pin "1") (pinfunction "K_1") (pintype "passive"))
      (node (ref "R160") (pin "2") (pinfunction "2_2") (pintype "passive"))
    )
    (net (code "65") (name "Net-(D_CLAMP_8-A)") (class "Default")
      (node (ref "D_CLAMP_8") (pin "2") (pinfunction "A_2") (pintype "passive"))
      (node (ref "D_CLAMP_9") (pin "1") (pinfunction "K_1") (pintype "passive"))
    )
    (net (code "66") (name "Net-(D_CLAMP_10-A)") (class "Default")
      (node (ref "D_CLAMP_10") (pin "2") (pinfunction "A_2") (pintype "passive"))
      (node (ref "D_CLAMP_11") (pin "1") (pinfunction "K_1") (pintype "passive"))
    )
    (net (code "67") (name "Net-(D_CLAMP_10-K)") (class "Default")
      (node (ref "D_CLAMP_10") (pin "1") (pinfunction "K_1") (pintype "passive"))
      (node (ref "D_CLAMP_9") (pin "2") (pinfunction "A_2") (pintype "passive"))
      (node (ref "R160") (pin "1") (pinfunction "1_1") (pintype "passive"))
    )
    (net (code "68") (name "Net-(D_CLAMP_11-A)") (class "Default")
      (node (ref "D_CLAMP_11") (pin "2") (pinfunction "A_2") (pintype "passive"))
      (node (ref "D_CLAMP_12") (pin "1") (pinfunction "K_1") (pintype "passive"))
    )
    (net (code "69") (name "Net-(D_CLAMP_12-A)") (class "Default")
      (node (ref "D_CLAMP_12") (pin "2") (pinfunction "A_2") (pintype "passive"))
      (node (ref "D_CLAMP_13") (pin "1") (pinfunction "K_1") (pintype "passive"))
    )
    (net (code "70") (name "Net-(D_CLAMP_13-A)") (class "Default")
      (node (ref "D_CLAMP_13") (pin "2") (pinfunction "A_2") (pintype "passive"))
      (node (ref "D_CLAMP_14") (pin "1") (pinfunction "K_1") (pintype "passive"))
    )
    (net (code "71") (name "Net-(D_CLAMP_14-A)") (class "Default")
      (node (ref "D_CLAMP_14") (pin "2") (pinfunction "A_2") (pintype "passive"))
      (node (ref "D_CLAMP_15") (pin "1") (pinfunction "K_1") (pintype "passive"))
    )
    (net (code "72") (name "Net-(D_CLAMP_15-A)") (class "Default")
      (node (ref "D_CLAMP_15") (pin "2") (pinfunction "A_2") (pintype "passive"))
      (node (ref "D_CLAMP_16") (pin "1") (pinfunction "K_1") (pintype "passive"))
    )
    (net (code "73") (name "Net-(J1-Pad10)") (class "Default")
      (node (ref "J1") (pin "10") (pinfunction "10_10") (pintype "passive"))
      (node (ref "R101") (pin "2") (pinfunction "2_2") (pintype "passive"))
    )
    (net (code "74") (name "Net-(J1-Pad12)") (class "Default")
      (node (ref "J1") (pin "12") (pinfunction "12_12") (pintype "passive"))
      (node (ref "R100") (pin "2") (pinfunction "2_2") (pintype "passive"))
    )
    (net (code "75") (name "Net-(J1-SHIELD-PadS1)") (class "Default")
      (node (ref "J1") (pin "S1") (pinfunction "SHIELD_S1") (pintype "passive"))
      (node (ref "J1") (pin "S2") (pinfunction "SHIELD_S2") (pintype "passive"))
    )
    (net (code "76") (name "Net-(J2-Pad10)") (class "Default")
      (node (ref "J2") (pin "10") (pinfunction "10_10") (pintype "passive"))
      (node (ref "R102") (pin "2") (pinfunction "2_2") (pintype "passive"))
    )
    (net (code "77") (name "Net-(J2-Pad12)") (class "Default")
      (node (ref "J2") (pin "12") (pinfunction "12_12") (pintype "passive"))
      (node (ref "R103") (pin "2") (pinfunction "2_2") (pintype "passive"))
    )
    (net (code "78") (name "Net-(J2-SHIELD-PadS1)") (class "Default")
      (node (ref "J2") (pin "S1") (pinfunction "SHIELD_S1") (pintype "passive"))
      (node (ref "J2") (pin "S2") (pinfunction "SHIELD_S2") (pintype "passive"))
    )
    (net (code "79") (name "Net-(Q_LEDA-D)") (class "Default")
      (node (ref "Q_LEDA") (pin "3") (pinfunction "D_3") (pintype "passive"))
      (node (ref "Q_LEDB") (pin "1") (pinfunction "G_1") (pintype "passive"))
      (node (ref "R_LEDB_O") (pin "1") (pinfunction "1_1") (pintype "passive"))
    )
    (net (code "80") (name "Net-(Q_LEDB-D)") (class "Default")
      (node (ref "Q_LEDB") (pin "3") (pinfunction "D_3") (pintype "passive"))
      (node (ref "R_LEDA_O") (pin "1") (pinfunction "1_1") (pintype "passive"))
    )
    (net (code "81") (name "Net-(R_1A_a-Pad2)") (class "Default")
      (node (ref "R_1A_a") (pin "2") (pinfunction "2_2") (pintype "passive"))
      (node (ref "R_1A_b") (pin "1") (pinfunction "1_1") (pintype "passive"))
    )
    (net (code "82") (name "Net-(R_1B_a-Pad2)") (class "Default")
      (node (ref "R_1B_a") (pin "2") (pinfunction "2_2") (pintype "passive"))
      (node (ref "R_1B_b") (pin "1") (pinfunction "1_1") (pintype "passive"))
    )
    (net (code "83") (name "Net-(U5V-Vout)") (class "Default")
      (node (ref "R17") (pin "1") (pinfunction "1_1") (pintype "passive"))
      (node (ref "U5V") (pin "3") (pinfunction "Vout_3") (pintype "output"))
    )
    (net (code "84") (name "PGND") (class "Default")
      (node (ref "D12") (pin "2") (pinfunction "A_2") (pintype "passive"))
      (node (ref "D9") (pin "2") (pinfunction "A_2") (pintype "passive"))
      (node (ref "Q3") (pin "3") (pinfunction "S_3") (pintype "passive"))
      (node (ref "Q4") (pin "3") (pinfunction "S_3") (pintype "passive"))
      (node (ref "R22") (pin "1") (pinfunction "1_1") (pintype "passive"))
      (node (ref "R23") (pin "2") (pinfunction "2_2") (pintype "passive"))
      (node (ref "R40") (pin "1") (pinfunction "1_1") (pintype "passive"))
      (node (ref "R8") (pin "2") (pinfunction "2_2") (pintype "passive"))
    )
    (net (code "85") (name "VIN_P") (class "Default")
      (node (ref "C41") (pin "2") (pinfunction "2_2") (pintype "passive"))
      (node (ref "C45") (pin "2") (pinfunction "2_2") (pintype "passive"))
      (node (ref "C46") (pin "2") (pinfunction "2_2") (pintype "passive"))
      (node (ref "C52") (pin "2") (pinfunction "2_2") (pintype "passive"))
      (node (ref "C620") (pin "2") (pinfunction "2_2") (pintype "passive"))
      (node (ref "D1_a") (pin "1") (pinfunction "K_1") (pintype "passive"))
      (node (ref "D1_b") (pin "1") (pinfunction "K_1") (pintype "passive"))
      (node (ref "D1_c") (pin "1") (pinfunction "K_1") (pintype "passive"))
      (node (ref "D1_d") (pin "1") (pinfunction "K_1") (pintype "passive"))
      (node (ref "D1_e") (pin "1") (pinfunction "K_1") (pintype "passive"))
      (node (ref "D1_f") (pin "1") (pinfunction "K_1") (pintype "passive"))
      (node (ref "D2_a") (pin "1") (pinfunction "K_1") (pintype "passive"))
      (node (ref "D2_b") (pin "1") (pinfunction "K_1") (pintype "passive"))
      (node (ref "D2_c") (pin "1") (pinfunction "K_1") (pintype "passive"))
      (node (ref "D2_d") (pin "1") (pinfunction "K_1") (pintype "passive"))
      (node (ref "D2_e") (pin "1") (pinfunction "K_1") (pintype "passive"))
      (node (ref "D2_f") (pin "1") (pinfunction "K_1") (pintype "passive"))
      (node (ref "D_CLAMP_1") (pin "1") (pinfunction "K_1") (pintype "passive"))
      (node (ref "R1") (pin "2") (pinfunction "2_2") (pintype "passive"))
      (node (ref "R11") (pin "2") (pinfunction "2_2") (pintype "passive"))
      (node (ref "R53") (pin "2") (pinfunction "2_2") (pintype "passive"))
      (node (ref "RVIN") (pin "2") (pinfunction "2_2") (pintype "passive"))
      (node (ref "U") (pin "33") (pinfunction "CSPIN_33") (pintype "input"))
    )
    (net (code "86") (name "VOUT_N") (class "Default")
      (node (ref "C50") (pin "2") (pinfunction "2_2") (pintype "passive"))
      (node (ref "C51") (pin "2") (pinfunction "2_2") (pintype "passive"))
      (node (ref "C54") (pin "2") (pinfunction "2_2") (pintype "passive"))
      (node (ref "C55") (pin "2") (pinfunction "2_2") (pintype "passive"))
      (node (ref "C65") (pin "2") (pinfunction "2_2") (pintype "passive"))
      (node (ref "R10") (pin "2") (pinfunction "2_2") (pintype "passive"))
      (node (ref "R13") (pin "2") (pinfunction "2_2") (pintype "passive"))
      (node (ref "RVCC") (pin "2") (pinfunction "2_2") (pintype "passive"))
      (node (ref "U") (pin "30") (pinfunction "CSNOUT_30") (pintype "input"))
    )
  )
)
